# EEZ_DIB_MCU_r2B4.net
KiCad netlist of a schematic drawn in EAGLE
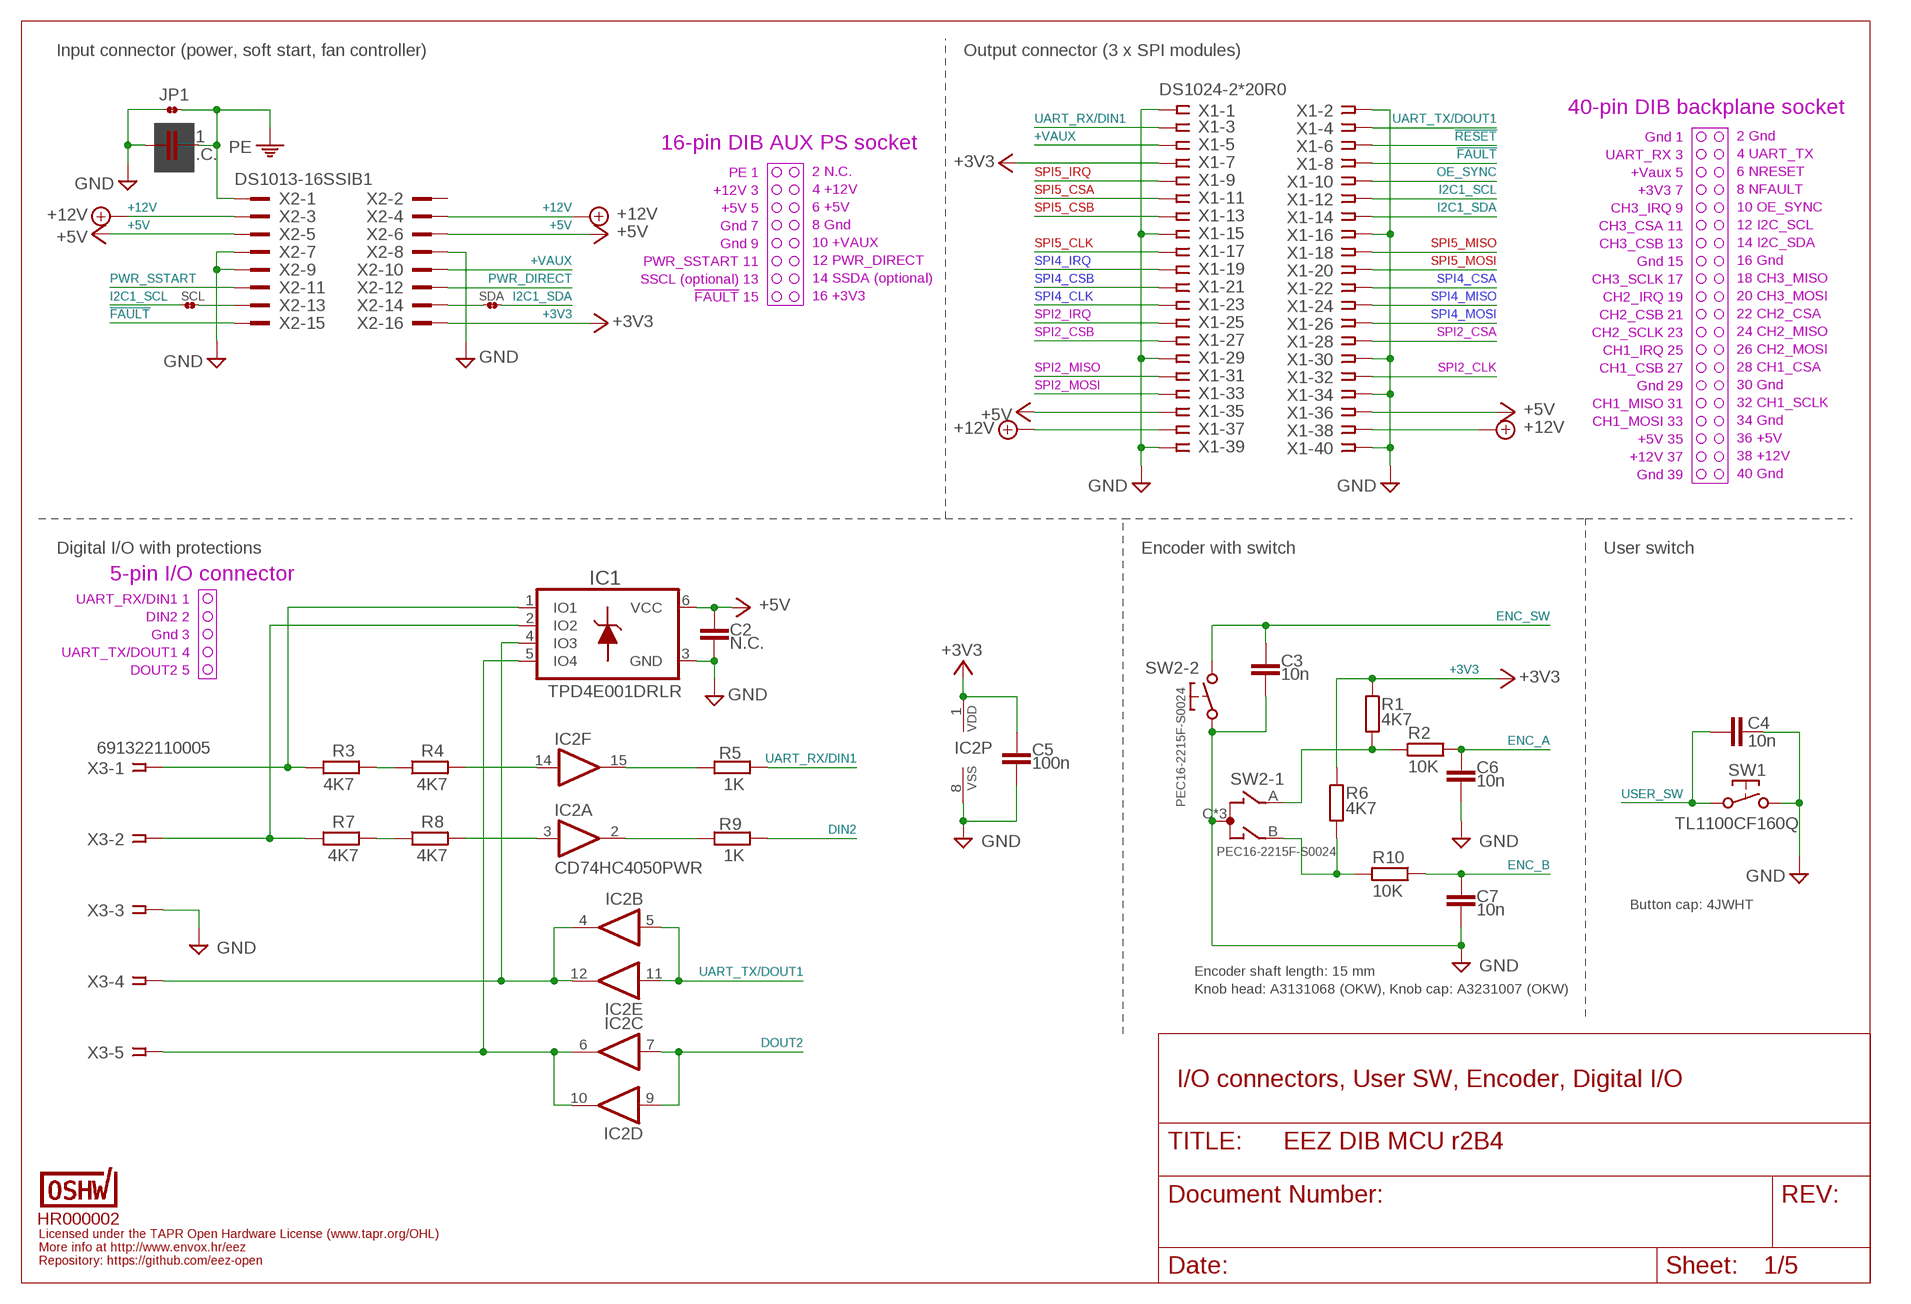
[diagram p0: schematic, sheet 1]
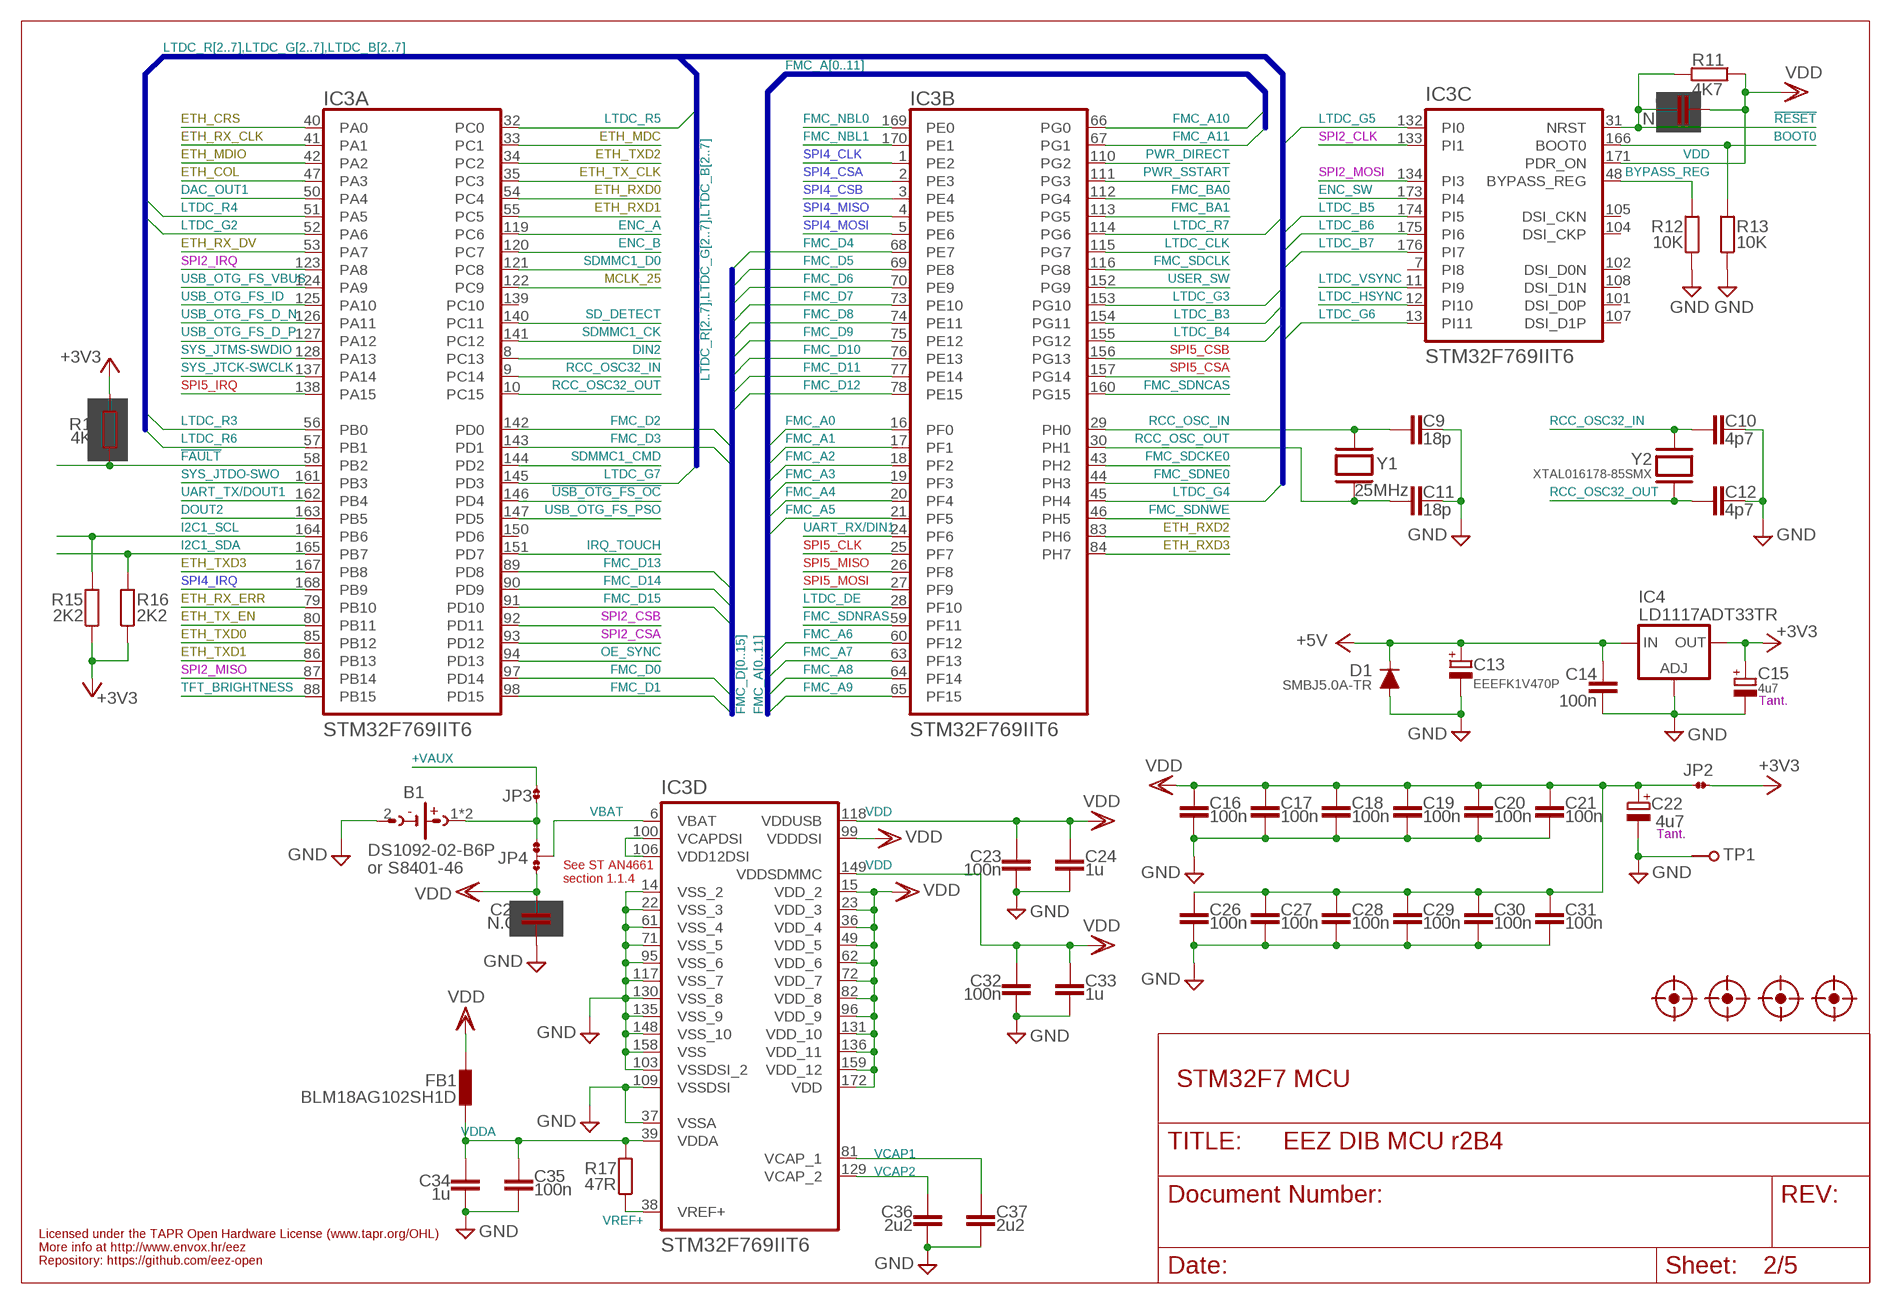
[diagram p1: schematic, sheet 2]
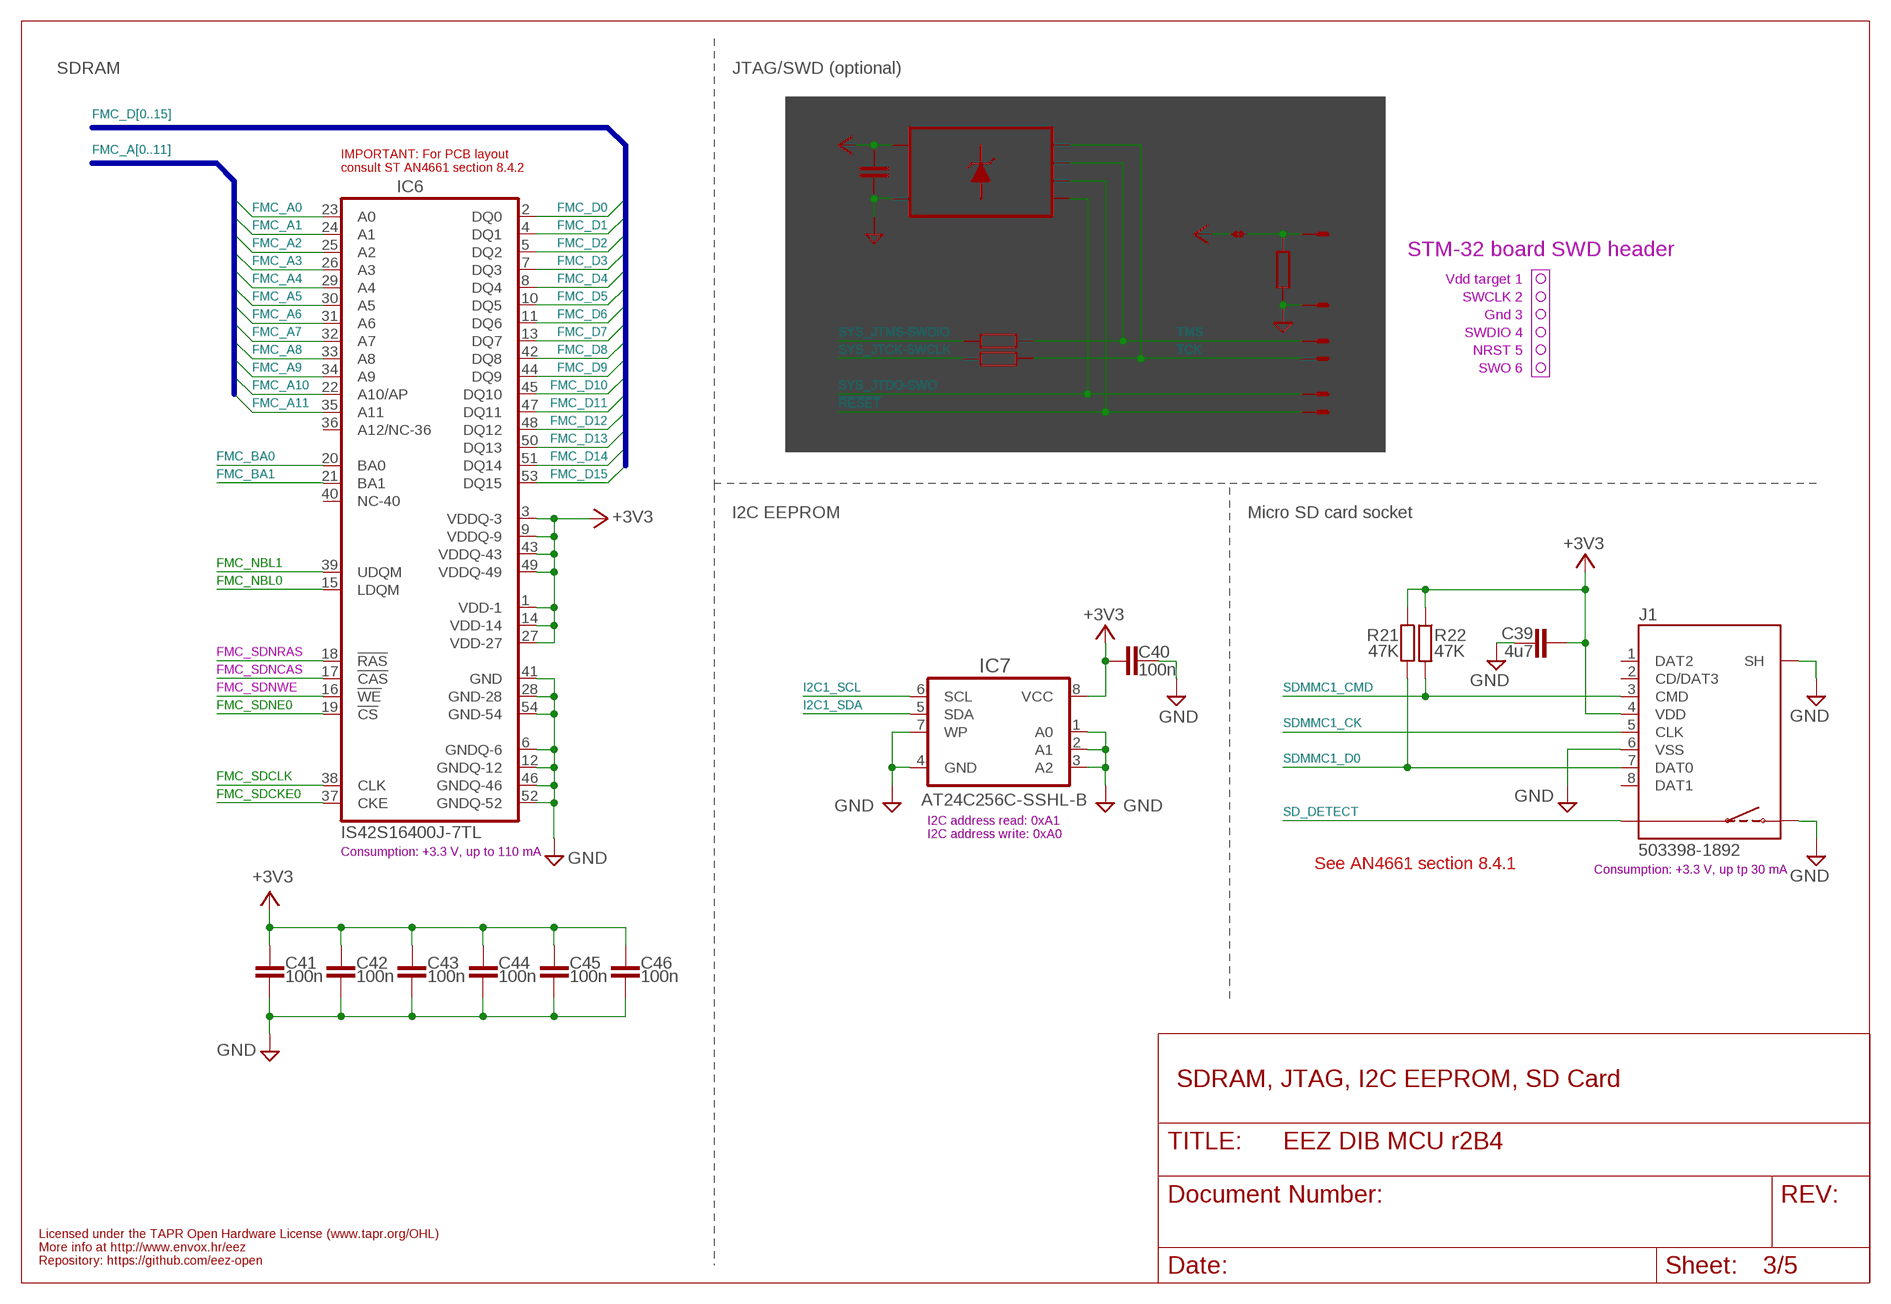
[diagram p2: schematic, sheet 3]
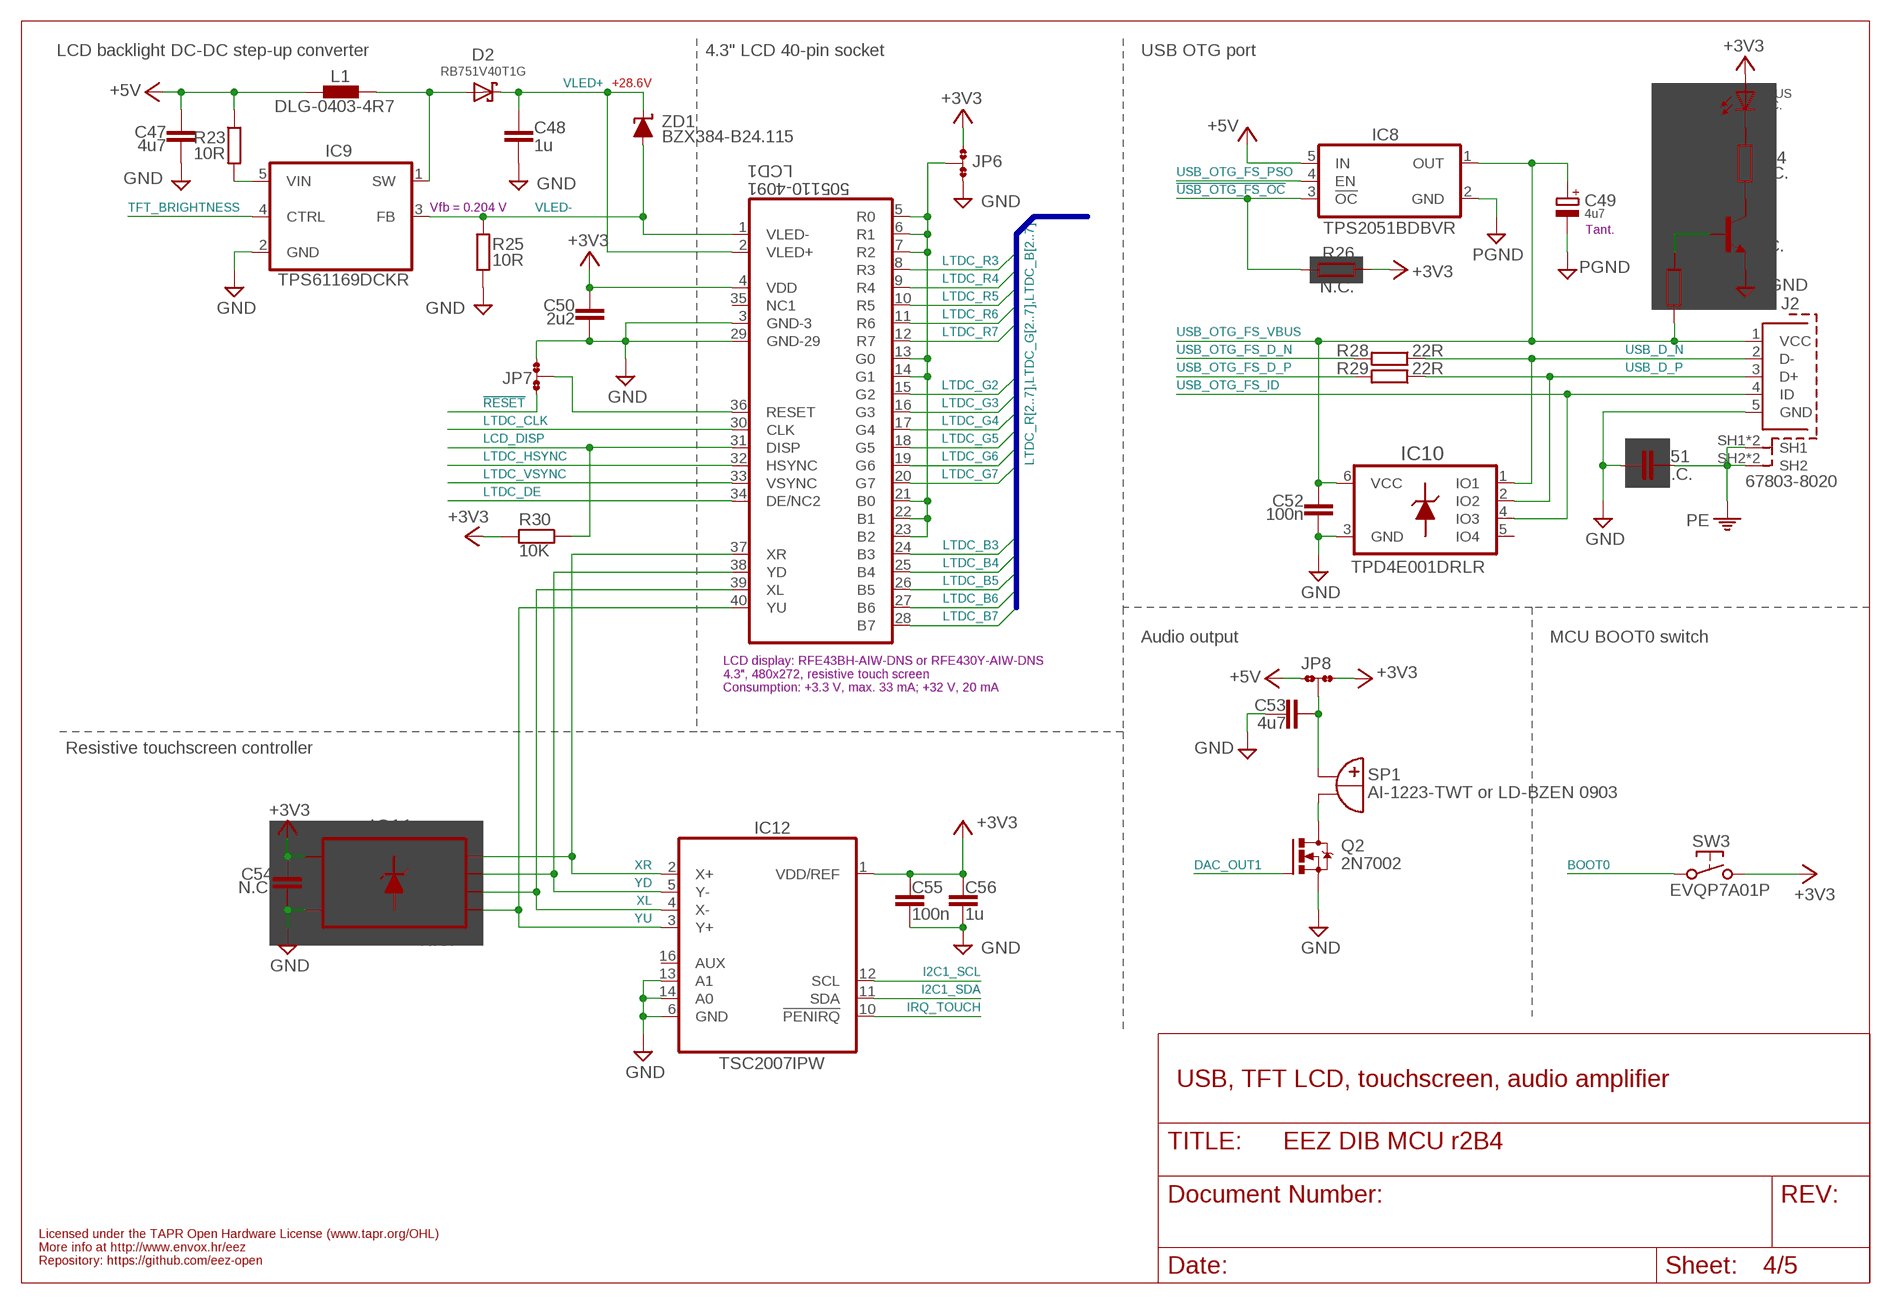
[diagram p3: schematic, sheet 4]
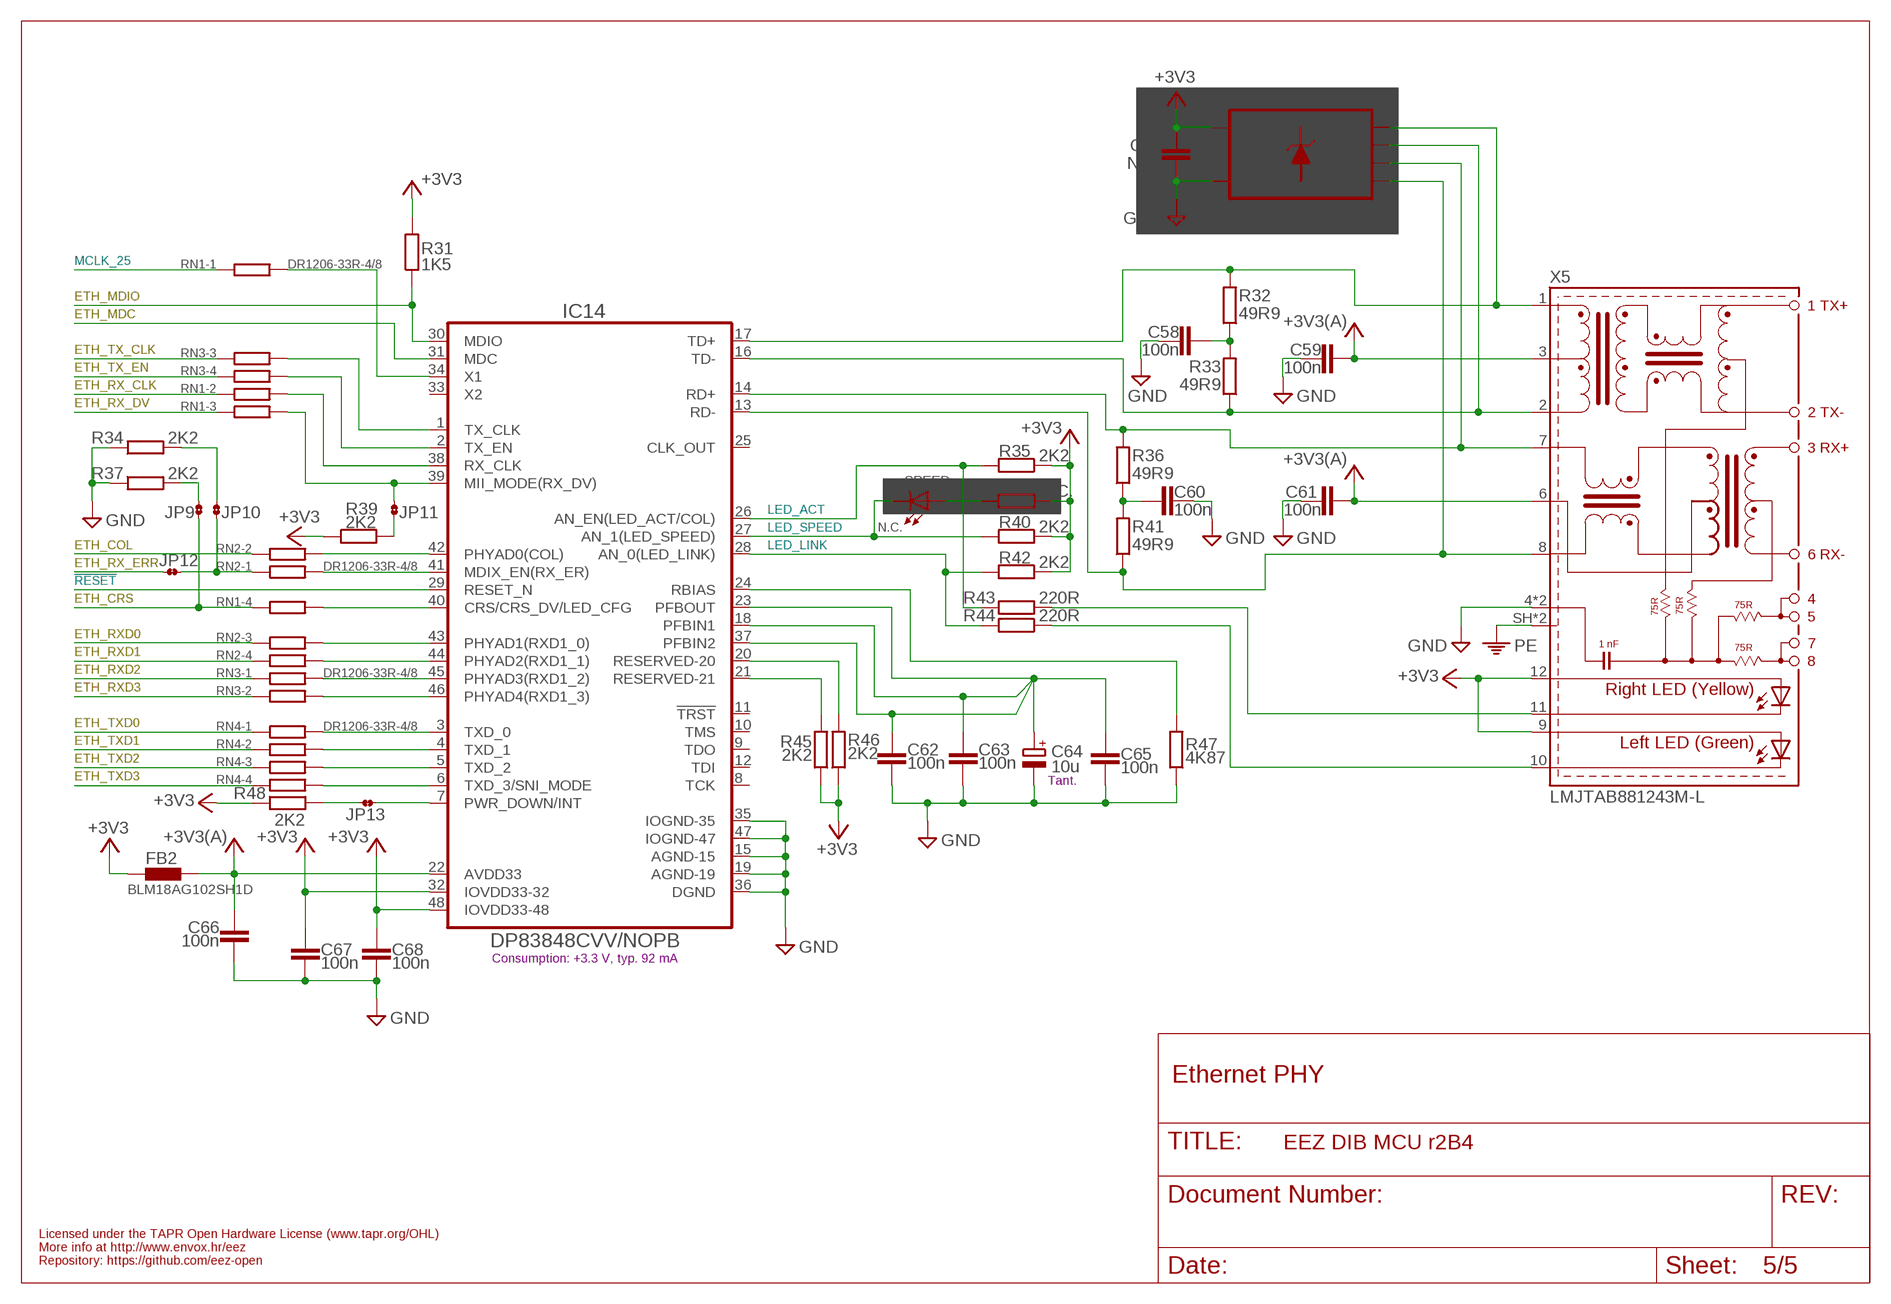
[diagram p4: schematic, sheet 5]

(export (version "E")
  (design (tool "Eeschema 10.0.6"))
  (components
    (comp (ref "B1")
      (value "DS1092-02-B6P")
      (footprint "eagle-import:S8401-46")
      (libsource (lib "eagle-import") (part "CELL_BATTERYVERT"))
    )
    (comp (ref "C8")
      (value "N.C.")
      (footprint "eagle-import:C0805")
      (libsource (lib "eagle-import") (part "C-EUC0805"))
    )
    (comp (ref "C9")
      (value "18p")
      (footprint "eagle-import:C0603")
      (libsource (lib "eagle-import") (part "C-EUC0603"))
    )
    (comp (ref "C10")
      (value "4p7")
      (footprint "eagle-import:C0603")
      (libsource (lib "eagle-import") (part "C-EUC0603"))
    )
    (comp (ref "C11")
      (value "18p")
      (footprint "eagle-import:C0603")
      (libsource (lib "eagle-import") (part "C-EUC0603"))
    )
    (comp (ref "C12")
      (value "4p7")
      (footprint "eagle-import:C0603")
      (libsource (lib "eagle-import") (part "C-EUC0603"))
    )
    (comp (ref "C13")
      (value "EEEFK1V470P")
      (footprint "eagle-import:CAPAE660X610N")
      (libsource (lib "eagle-import") (part "ECAPPANASONIC_H"))
    )
    (comp (ref "C14")
      (value "100n")
      (footprint "eagle-import:C0603")
      (libsource (lib "eagle-import") (part "C-EUC0603"))
    )
    (comp (ref "C15")
      (value "4u7")
      (footprint "eagle-import:EC1206")
      (libsource (lib "eagle-import") (part "ECAP1206"))
    )
    (comp (ref "C16")
      (value "100n")
      (footprint "eagle-import:C0603")
      (libsource (lib "eagle-import") (part "C-EUC0603"))
    )
    (comp (ref "C17")
      (value "100n")
      (footprint "eagle-import:C0603")
      (libsource (lib "eagle-import") (part "C-EUC0603"))
    )
    (comp (ref "C18")
      (value "100n")
      (footprint "eagle-import:C0603")
      (libsource (lib "eagle-import") (part "C-EUC0603"))
    )
    (comp (ref "C19")
      (value "100n")
      (footprint "eagle-import:C0603")
      (libsource (lib "eagle-import") (part "C-EUC0603"))
    )
    (comp (ref "C20")
      (value "100n")
      (footprint "eagle-import:C0603")
      (libsource (lib "eagle-import") (part "C-EUC0603"))
    )
    (comp (ref "C21")
      (value "100n")
      (footprint "eagle-import:C0603")
      (libsource (lib "eagle-import") (part "C-EUC0603"))
    )
    (comp (ref "C22")
      (value "4u7")
      (footprint "eagle-import:EC1206")
      (libsource (lib "eagle-import") (part "ECAP1206"))
    )
    (comp (ref "C23")
      (value "100n")
      (footprint "eagle-import:C0603")
      (libsource (lib "eagle-import") (part "C-EUC0603"))
    )
    (comp (ref "C24")
      (value "1u")
      (footprint "eagle-import:C0805")
      (libsource (lib "eagle-import") (part "C-EUC0805"))
    )
    (comp (ref "C25")
      (value "N.C.")
      (footprint "eagle-import:C0603")
      (libsource (lib "eagle-import") (part "C-EUC0603"))
    )
    (comp (ref "C26")
      (value "100n")
      (footprint "eagle-import:C0603")
      (libsource (lib "eagle-import") (part "C-EUC0603"))
    )
    (comp (ref "C27")
      (value "100n")
      (footprint "eagle-import:C0603")
      (libsource (lib "eagle-import") (part "C-EUC0603"))
    )
    (comp (ref "C28")
      (value "100n")
      (footprint "eagle-import:C0603")
      (libsource (lib "eagle-import") (part "C-EUC0603"))
    )
    (comp (ref "C29")
      (value "100n")
      (footprint "eagle-import:C0603")
      (libsource (lib "eagle-import") (part "C-EUC0603"))
    )
    (comp (ref "C30")
      (value "100n")
      (footprint "eagle-import:C0603")
      (libsource (lib "eagle-import") (part "C-EUC0603"))
    )
    (comp (ref "C31")
      (value "100n")
      (footprint "eagle-import:C0603")
      (libsource (lib "eagle-import") (part "C-EUC0603"))
    )
    (comp (ref "C32")
      (value "100n")
      (footprint "eagle-import:C0603")
      (libsource (lib "eagle-import") (part "C-EUC0603"))
    )
    (comp (ref "C33")
      (value "1u")
      (footprint "eagle-import:C0805")
      (libsource (lib "eagle-import") (part "C-EUC0805"))
    )
    (comp (ref "C34")
      (value "1u")
      (footprint "eagle-import:C0805")
      (libsource (lib "eagle-import") (part "C-EUC0805"))
    )
    (comp (ref "C35")
      (value "100n")
      (footprint "eagle-import:C0603")
      (libsource (lib "eagle-import") (part "C-EUC0603"))
    )
    (comp (ref "C36")
      (value "2u2")
      (footprint "eagle-import:C0805")
      (libsource (lib "eagle-import") (part "C-EUC0805"))
    )
    (comp (ref "C37")
      (value "2u2")
      (footprint "eagle-import:C0805")
      (libsource (lib "eagle-import") (part "C-EUC0805"))
    )
    (comp (ref "D1")
      (value "SMBJ5.0A-TR")
      (footprint "eagle-import:DO214AA")
      (libsource (lib "eagle-import") (part "DIODEDO214AA"))
    )
    (comp (ref "FB1")
      (value "BLM18AG102SH1D")
      (footprint "eagle-import:BEAD0603")
      (libsource (lib "eagle-import") (part "FERRITE_BEAD0603"))
    )
    (comp (ref "FM1")
      (value "FIDUCIAL")
      (footprint "eagle-import:FIDUCIAL")
      (libsource (lib "eagle-import") (part "FIDUCIAL"))
    )
    (comp (ref "FM2")
      (value "FIDUCIAL")
      (footprint "eagle-import:FIDUCIAL")
      (libsource (lib "eagle-import") (part "FIDUCIAL"))
    )
    (comp (ref "FM3")
      (value "FIDUCIAL")
      (footprint "eagle-import:FIDUCIAL")
      (libsource (lib "eagle-import") (part "FIDUCIAL"))
    )
    (comp (ref "FM4")
      (value "FIDUCIAL")
      (footprint "eagle-import:FIDUCIAL")
      (libsource (lib "eagle-import") (part "FIDUCIAL"))
    )
    (comp (ref "IC3")
      (value "STM32F769IIT6")
      (footprint "eagle-import:LQFP-176_24X24MM")
      (fields
        (field (name "MANUFACTURER_PART_NUMBER") "stm32f769ixt")
        (field (name "COPYRIGHT") "Copyright C 2016 Accelerated Designs. All rights reserved")
      )
      (libsource (lib "eagle-import") (part "STM32F769IXT"))
    )
    (comp (ref "IC4")
      (value "LD1117ADT33TR")
      (footprint "eagle-import:DPACK")
      (libsource (lib "eagle-import") (part "LD117A?DT33TR"))
    )
    (comp (ref "JP2")
      (value "JP2-NOCUT")
      (footprint "eagle-import:JP2-NOCUT")
      (libsource (lib "eagle-import") (part "JP2-NOCUT"))
    )
    (comp (ref "JP3")
      (value "JP2-CUT")
      (footprint "eagle-import:JP2-CUT")
      (libsource (lib "eagle-import") (part "JP2-CUT"))
    )
    (comp (ref "JP4")
      (value "JP3-CUT")
      (footprint "eagle-import:JP3-CUT")
      (libsource (lib "eagle-import") (part "JP3-CUT"))
    )
    (comp (ref "R11")
      (value "4K7")
      (footprint "eagle-import:R0805")
      (libsource (lib "eagle-import") (part "R-EU_R0805"))
    )
    (comp (ref "R12")
      (value "10K")
      (footprint "eagle-import:R0805")
      (libsource (lib "eagle-import") (part "R-EU_R0805"))
    )
    (comp (ref "R13")
      (value "10K")
      (footprint "eagle-import:R0805")
      (libsource (lib "eagle-import") (part "R-EU_R0805"))
    )
    (comp (ref "R14")
      (value "4K7")
      (footprint "eagle-import:R0805")
      (libsource (lib "eagle-import") (part "R-EU_R0805"))
    )
    (comp (ref "R15")
      (value "2K2")
      (footprint "eagle-import:R0805")
      (libsource (lib "eagle-import") (part "R-EU_R0805"))
    )
    (comp (ref "R16")
      (value "2K2")
      (footprint "eagle-import:R0805")
      (libsource (lib "eagle-import") (part "R-EU_R0805"))
    )
    (comp (ref "R17")
      (value "47R")
      (footprint "eagle-import:R0805")
      (libsource (lib "eagle-import") (part "R-EU_R0805"))
    )
    (comp (ref "TP1")
      (value "PCB_TEST_TABSHIELD")
      (footprint "eagle-import:PCB_SHIELD_TAB")
      (libsource (lib "eagle-import") (part "PCB_TEST_TABSHIELD"))
    )
    (comp (ref "Y1")
      (value "25MHz")
      (footprint "eagle-import:HC-49_4H")
      (libsource (lib "eagle-import") (part "XTALSMD"))
    )
    (comp (ref "Y2")
      (value "XTAL016178-85SMX")
      (footprint "eagle-import:85SMX")
      (libsource (lib "eagle-import") (part "XTAL85SMX"))
    )
    (comp (ref "C57")
      (value "N.C.")
      (footprint "eagle-import:C0603")
      (libsource (lib "eagle-import") (part "C-EUC0603"))
    )
    (comp (ref "C58")
      (value "100n")
      (footprint "eagle-import:C0603")
      (libsource (lib "eagle-import") (part "C-EUC0603"))
    )
    (comp (ref "C59")
      (value "100n")
      (footprint "eagle-import:C0603")
      (libsource (lib "eagle-import") (part "C-EUC0603"))
    )
    (comp (ref "C60")
      (value "100n")
      (footprint "eagle-import:C0603")
      (libsource (lib "eagle-import") (part "C-EUC0603"))
    )
    (comp (ref "C61")
      (value "100n")
      (footprint "eagle-import:C0603")
      (libsource (lib "eagle-import") (part "C-EUC0603"))
    )
    (comp (ref "C62")
      (value "100n")
      (footprint "eagle-import:C0603")
      (libsource (lib "eagle-import") (part "C-EUC0603"))
    )
    (comp (ref "C63")
      (value "100n")
      (footprint "eagle-import:C0603")
      (libsource (lib "eagle-import") (part "C-EUC0603"))
    )
    (comp (ref "C64")
      (value "10u")
      (footprint "eagle-import:EC1206")
      (libsource (lib "eagle-import") (part "ECAP1206"))
    )
    (comp (ref "C65")
      (value "100n")
      (footprint "eagle-import:C0603")
      (libsource (lib "eagle-import") (part "C-EUC0603"))
    )
    (comp (ref "C66")
      (value "100n")
      (footprint "eagle-import:C0603")
      (libsource (lib "eagle-import") (part "C-EUC0603"))
    )
    (comp (ref "C67")
      (value "100n")
      (footprint "eagle-import:C0603")
      (libsource (lib "eagle-import") (part "C-EUC0603"))
    )
    (comp (ref "C68")
      (value "100n")
      (footprint "eagle-import:C0603")
      (libsource (lib "eagle-import") (part "C-EUC0603"))
    )
    (comp (ref "FB2")
      (value "BLM18AG102SH1D")
      (footprint "eagle-import:BEAD0603")
      (libsource (lib "eagle-import") (part "FERRITE_BEAD0603"))
    )
    (comp (ref "IC13")
      (value "N.C.")
      (footprint "eagle-import:DRL6")
      (libsource (lib "eagle-import") (part "TPD4E001-DRL"))
    )
    (comp (ref "IC14")
      (value "DP83848CVV/NOPB")
      (footprint "eagle-import:PT48")
      (libsource (lib "eagle-import") (part "DP83848CVV/NOPB"))
    )
    (comp (ref "JP9")
      (value "JP2-CUT")
      (footprint "eagle-import:JP2-CUT")
      (libsource (lib "eagle-import") (part "JP2-CUT"))
    )
    (comp (ref "JP10")
      (value "JP2-CUT")
      (footprint "eagle-import:JP2-CUT")
      (libsource (lib "eagle-import") (part "JP2-CUT"))
    )
    (comp (ref "JP11")
      (value "JP2-CUT")
      (footprint "eagle-import:JP2-CUT")
      (libsource (lib "eagle-import") (part "JP2-CUT"))
    )
    (comp (ref "JP12")
      (value "JP2-NOCUT")
      (footprint "eagle-import:JP2-NOCUT")
      (libsource (lib "eagle-import") (part "JP2-NOCUT"))
    )
    (comp (ref "JP13")
      (value "JP2-NOCUT")
      (footprint "eagle-import:JP2-NOCUT")
      (libsource (lib "eagle-import") (part "JP2-NOCUT"))
    )
    (comp (ref "R31")
      (value "1K5")
      (footprint "eagle-import:R0805")
      (libsource (lib "eagle-import") (part "R-EU_R0805"))
    )
    (comp (ref "R32")
      (value "49R9")
      (footprint "eagle-import:R0805")
      (libsource (lib "eagle-import") (part "R-EU_R0805"))
    )
    (comp (ref "R33")
      (value "49R9")
      (footprint "eagle-import:R0805")
      (libsource (lib "eagle-import") (part "R-EU_R0805"))
    )
    (comp (ref "R34")
      (value "2K2")
      (footprint "eagle-import:R0805")
      (libsource (lib "eagle-import") (part "R-EU_R0805"))
    )
    (comp (ref "R35")
      (value "2K2")
      (footprint "eagle-import:R0805")
      (libsource (lib "eagle-import") (part "R-EU_R0805"))
    )
    (comp (ref "R36")
      (value "49R9")
      (footprint "eagle-import:R0805")
      (libsource (lib "eagle-import") (part "R-EU_R0805"))
    )
    (comp (ref "R37")
      (value "2K2")
      (footprint "eagle-import:R0805")
      (libsource (lib "eagle-import") (part "R-EU_R0805"))
    )
    (comp (ref "R38")
      (value "N.C.")
      (footprint "eagle-import:R0805")
      (libsource (lib "eagle-import") (part "R-EU_R0805"))
    )
    (comp (ref "R39")
      (value "2K2")
      (footprint "eagle-import:R0805")
      (libsource (lib "eagle-import") (part "R-EU_R0805"))
    )
    (comp (ref "R40")
      (value "2K2")
      (footprint "eagle-import:R0805")
      (libsource (lib "eagle-import") (part "R-EU_R0805"))
    )
    (comp (ref "R41")
      (value "49R9")
      (footprint "eagle-import:R0805")
      (libsource (lib "eagle-import") (part "R-EU_R0805"))
    )
    (comp (ref "R42")
      (value "2K2")
      (footprint "eagle-import:R0805")
      (libsource (lib "eagle-import") (part "R-EU_R0805"))
    )
    (comp (ref "R43")
      (value "220R")
      (footprint "eagle-import:R0805")
      (libsource (lib "eagle-import") (part "R-EU_R0805"))
    )
    (comp (ref "R44")
      (value "220R")
      (footprint "eagle-import:R0805")
      (libsource (lib "eagle-import") (part "R-EU_R0805"))
    )
    (comp (ref "R45")
      (value "2K2")
      (footprint "eagle-import:R0805")
      (libsource (lib "eagle-import") (part "R-EU_R0805"))
    )
    (comp (ref "R46")
      (value "2K2")
      (footprint "eagle-import:R0805")
      (libsource (lib "eagle-import") (part "R-EU_R0805"))
    )
    (comp (ref "R47")
      (value "4K87")
      (footprint "eagle-import:R0805")
      (libsource (lib "eagle-import") (part "R-EU_R0805"))
    )
    (comp (ref "R48")
      (value "2K2")
      (footprint "eagle-import:R0805")
      (libsource (lib "eagle-import") (part "R-EU_R0805"))
    )
    (comp (ref "RN1")
      (value "DR1206-33R-4/8")
      (footprint "eagle-import:CAY16")
      (libsource (lib "eagle-import") (part "R_ARRAY4"))
    )
    (comp (ref "RN2")
      (value "DR1206-33R-4/8")
      (footprint "eagle-import:CAY16")
      (libsource (lib "eagle-import") (part "R_ARRAY4"))
    )
    (comp (ref "RN3")
      (value "DR1206-33R-4/8")
      (footprint "eagle-import:CAY16")
      (libsource (lib "eagle-import") (part "R_ARRAY4"))
    )
    (comp (ref "RN4")
      (value "DR1206-33R-4/8")
      (footprint "eagle-import:CAY16")
      (libsource (lib "eagle-import") (part "R_ARRAY4"))
    )
    (comp (ref "SPEED")
      (value "N.C.")
      (footprint "eagle-import:LED_0805")
      (libsource (lib "eagle-import") (part "LED0805"))
    )
    (comp (ref "X5")
      (value "LMJTAB881243M-L")
      (footprint "eagle-import:RJ45-TRAFO-LED")
      (libsource (lib "eagle-import") (part "RJ45-TRAFO-LED"))
    )
    (comp (ref "C47")
      (value "4u7")
      (footprint "eagle-import:C1206")
      (libsource (lib "eagle-import") (part "C-EUC1206"))
    )
    (comp (ref "C48")
      (value "1u")
      (footprint "eagle-import:C0805")
      (libsource (lib "eagle-import") (part "C-EUC0805"))
    )
    (comp (ref "C49")
      (value "4u7")
      (footprint "eagle-import:EC1206")
      (libsource (lib "eagle-import") (part "ECAP1206"))
    )
    (comp (ref "C50")
      (value "2u2")
      (footprint "eagle-import:C0805")
      (libsource (lib "eagle-import") (part "C-EUC0805"))
    )
    (comp (ref "C51")
      (value "N.C.")
      (footprint "eagle-import:C0805")
      (libsource (lib "eagle-import") (part "C-EUC0805"))
    )
    (comp (ref "C52")
      (value "100n")
      (footprint "eagle-import:C0603")
      (libsource (lib "eagle-import") (part "C-EUC0603"))
    )
    (comp (ref "C53")
      (value "4u7")
      (footprint "eagle-import:C1206")
      (libsource (lib "eagle-import") (part "C-EUC1206"))
    )
    (comp (ref "C54")
      (value "N.C.")
      (footprint "eagle-import:C0603")
      (libsource (lib "eagle-import") (part "C-EUC0603"))
    )
    (comp (ref "C55")
      (value "100n")
      (footprint "eagle-import:C0603")
      (libsource (lib "eagle-import") (part "C-EUC0603"))
    )
    (comp (ref "C56")
      (value "1u")
      (footprint "eagle-import:C0805")
      (libsource (lib "eagle-import") (part "C-EUC0805"))
    )
    (comp (ref "D2")
      (value "RB751V40T1G")
      (footprint "eagle-import:SOD323-R")
      (libsource (lib "eagle-import") (part "SCHOTTKYSOD-323R"))
    )
    (comp (ref "IC8")
      (value "TPS2051BDBVR")
      (footprint "eagle-import:DBV5")
      (libsource (lib "eagle-import") (part "TPS2051B"))
    )
    (comp (ref "IC9")
      (value "TPS61169DCKR")
      (footprint "eagle-import:DCK5")
      (fields (field (name "MANUFACTURER") "Texas Instruments"))
      (libsource (lib "eagle-import") (part "TPS61169DCKR"))
    )
    (comp (ref "IC10")
      (value "TPD4E001DRLR")
      (footprint "eagle-import:DRL6")
      (libsource (lib "eagle-import") (part "TPD4E001-DRL"))
    )
    (comp (ref "IC11")
      (value "N.C.")
      (footprint "eagle-import:DRL6")
      (libsource (lib "eagle-import") (part "TPD4E001-DRL"))
    )
    (comp (ref "IC12")
      (value "TSC2007IPW")
      (footprint "eagle-import:PW(R-PDSO-G16)")
      (libsource (lib "eagle-import") (part "TSC2007IPW"))
    )
    (comp (ref "J2")
      (value "67803-8020")
      (footprint "eagle-import:678038020")
      (libsource (lib "eagle-import") (part "678038020"))
    )
    (comp (ref "JP6")
      (value "JP3-CUT")
      (footprint "eagle-import:JP3-CUT")
      (libsource (lib "eagle-import") (part "JP3-CUT"))
    )
    (comp (ref "JP7")
      (value "JP3-CUT")
      (footprint "eagle-import:JP3-CUT")
      (libsource (lib "eagle-import") (part "JP3-CUT"))
    )
    (comp (ref "JP8")
      (value "JP3-CUT")
      (footprint "eagle-import:JP3-CUT")
      (libsource (lib "eagle-import") (part "JP3-CUT"))
    )
    (comp (ref "L1")
      (value "DLG-0403-4R7")
      (footprint "eagle-import:DE0403")
      (libsource (lib "eagle-import") (part "DE0403"))
    )
    (comp (ref "LCD1")
      (value "505110-4091")
      (footprint "eagle-import:FPC_40")
      (libsource (lib "eagle-import") (part "RFE430Y-AIW-DNS"))
    )
    (comp (ref "Q1")
      (value "N.C.")
      (footprint "eagle-import:SOT23-BEC")
      (libsource (lib "eagle-import") (part "-NPN-SOT23-BECMMBT5551LT1"))
    )
    (comp (ref "Q2")
      (value "2N7002")
      (footprint "eagle-import:SOT103P240X110-3N")
      (fields (field (name "MPN") "2N7002-7-F"))
      (libsource (lib "eagle-import") (part "2N7002"))
    )
    (comp (ref "R23")
      (value "10R")
      (footprint "eagle-import:R0805")
      (libsource (lib "eagle-import") (part "R-EU_R0805"))
    )
    (comp (ref "R24")
      (value "N.C.")
      (footprint "eagle-import:R0805")
      (libsource (lib "eagle-import") (part "R-EU_R0805"))
    )
    (comp (ref "R25")
      (value "10R")
      (footprint "eagle-import:R0805")
      (libsource (lib "eagle-import") (part "R-EU_R0805"))
    )
    (comp (ref "R26")
      (value "N.C.")
      (footprint "eagle-import:R0805")
      (libsource (lib "eagle-import") (part "R-EU_R0805"))
    )
    (comp (ref "R27")
      (value "N.C.")
      (footprint "eagle-import:R0805")
      (libsource (lib "eagle-import") (part "R-EU_R0805"))
    )
    (comp (ref "R28")
      (value "22R")
      (footprint "eagle-import:R0805")
      (libsource (lib "eagle-import") (part "R-EU_R0805"))
    )
    (comp (ref "R29")
      (value "22R")
      (footprint "eagle-import:R0805")
      (libsource (lib "eagle-import") (part "R-EU_R0805"))
    )
    (comp (ref "R30")
      (value "10K")
      (footprint "eagle-import:R0805")
      (libsource (lib "eagle-import") (part "R-EU_R0805"))
    )
    (comp (ref "SP1")
      (value "AI-1223-TWT or LD-BZEN 0903")
      (footprint "eagle-import:AI-1223-TWT_COMBO")
      (libsource (lib "eagle-import") (part "AI-1223-TWT-LDB0903"))
    )
    (comp (ref "SW3")
      (value "EVQP7A01P")
      (footprint "eagle-import:PANASONIC_EVQP")
      (libsource (lib "eagle-import") (part "EVQP7A01P"))
    )
    (comp (ref "VBUS")
      (value "N.C.")
      (footprint "eagle-import:LED_0805")
      (libsource (lib "eagle-import") (part "LED0805"))
    )
    (comp (ref "ZD1")
      (value "BZX384-B24.115")
      (footprint "eagle-import:SOD323-W")
      (libsource (lib "eagle-import") (part "ZENER-DIODESOD323"))
    )
    (comp (ref "C38")
      (value "N.C.")
      (footprint "eagle-import:C0603")
      (libsource (lib "eagle-import") (part "C-EUC0603"))
    )
    (comp (ref "C39")
      (value "4u7")
      (footprint "eagle-import:C1206")
      (libsource (lib "eagle-import") (part "C-EUC1206"))
    )
    (comp (ref "C40")
      (value "100n")
      (footprint "eagle-import:C0603")
      (libsource (lib "eagle-import") (part "C-EUC0603"))
    )
    (comp (ref "C41")
      (value "100n")
      (footprint "eagle-import:C0603")
      (libsource (lib "eagle-import") (part "C-EUC0603"))
    )
    (comp (ref "C42")
      (value "100n")
      (footprint "eagle-import:C0603")
      (libsource (lib "eagle-import") (part "C-EUC0603"))
    )
    (comp (ref "C43")
      (value "100n")
      (footprint "eagle-import:C0603")
      (libsource (lib "eagle-import") (part "C-EUC0603"))
    )
    (comp (ref "C44")
      (value "100n")
      (footprint "eagle-import:C0603")
      (libsource (lib "eagle-import") (part "C-EUC0603"))
    )
    (comp (ref "C45")
      (value "100n")
      (footprint "eagle-import:C0603")
      (libsource (lib "eagle-import") (part "C-EUC0603"))
    )
    (comp (ref "C46")
      (value "100n")
      (footprint "eagle-import:C0603")
      (libsource (lib "eagle-import") (part "C-EUC0603"))
    )
    (comp (ref "IC5")
      (value "N.C.")
      (footprint "eagle-import:DRL6")
      (libsource (lib "eagle-import") (part "TPD4E001-DRL"))
    )
    (comp (ref "IC6")
      (value "IS42S16400J-7TL")
      (footprint "eagle-import:TSOPII-54")
      (libsource (lib "eagle-import") (part "IS42S16400"))
    )
    (comp (ref "IC7")
      (value "AT24C256C-SSHL-B")
      (footprint "eagle-import:SOIC127P600X173-8N")
      (libsource (lib "eagle-import") (part "AT24CXXSOIC8"))
    )
    (comp (ref "J1")
      (value "503398-1892")
      (footprint "eagle-import:5033981892")
      (libsource (lib "eagle-import") (part "5033981892"))
    )
    (comp (ref "JP5")
      (value "JP2-CUT")
      (footprint "eagle-import:JP2-CUT")
      (libsource (lib "eagle-import") (part "JP2-CUT"))
    )
    (comp (ref "R18")
      (value "N.C.")
      (footprint "eagle-import:R0805")
      (libsource (lib "eagle-import") (part "R-EU_R0805"))
    )
    (comp (ref "R19")
      (value "N.C.")
      (footprint "eagle-import:R0805")
      (libsource (lib "eagle-import") (part "R-EU_R0805"))
    )
    (comp (ref "R20")
      (value "N.C.")
      (footprint "eagle-import:R0805")
      (libsource (lib "eagle-import") (part "R-EU_R0805"))
    )
    (comp (ref "R21")
      (value "47K")
      (footprint "eagle-import:R0805")
      (libsource (lib "eagle-import") (part "R-EU_R0805"))
    )
    (comp (ref "R22")
      (value "47K")
      (footprint "eagle-import:R0805")
      (libsource (lib "eagle-import") (part "R-EU_R0805"))
    )
    (comp (ref "X4")
      (value "N.C.")
      (footprint "eagle-import:22-23-2061")
      (fields (field (name "MF") "MOLEX") (field (name "MPN") "22-23-2061"))
      (libsource (lib "eagle-import") (part "22-23-2061"))
    )
    (comp (ref "C1")
      (value "N.C.")
      (footprint "eagle-import:C0805")
      (libsource (lib "eagle-import") (part "C-EUC0805"))
    )
    (comp (ref "C2")
      (value "N.C.")
      (footprint "eagle-import:C0603")
      (libsource (lib "eagle-import") (part "C-EUC0603"))
    )
    (comp (ref "C3")
      (value "10n")
      (footprint "eagle-import:C0805")
      (libsource (lib "eagle-import") (part "C-EUC0805"))
    )
    (comp (ref "C4")
      (value "10n")
      (footprint "eagle-import:C0805")
      (libsource (lib "eagle-import") (part "C-EUC0805"))
    )
    (comp (ref "C5")
      (value "100n")
      (footprint "eagle-import:C0603")
      (libsource (lib "eagle-import") (part "C-EUC0603"))
    )
    (comp (ref "C6")
      (value "10n")
      (footprint "eagle-import:C0805")
      (libsource (lib "eagle-import") (part "C-EUC0805"))
    )
    (comp (ref "C7")
      (value "10n")
      (footprint "eagle-import:C0805")
      (libsource (lib "eagle-import") (part "C-EUC0805"))
    )
    (comp (ref "IC1")
      (value "TPD4E001DRLR")
      (footprint "eagle-import:DRL6")
      (libsource (lib "eagle-import") (part "TPD4E001-DRL"))
    )
    (comp (ref "IC2")
      (value "CD74HC4050PWR")
      (footprint "eagle-import:PW16")
      (libsource (lib "eagle-import") (part "CD74HC4050PWR"))
    )
    (comp (ref "JP1")
      (value "JP2-NOCUT")
      (footprint "eagle-import:JP2-NOCUT")
      (libsource (lib "eagle-import") (part "JP2-NOCUT"))
    )
    (comp (ref "R1")
      (value "4K7")
      (footprint "eagle-import:R0805")
      (libsource (lib "eagle-import") (part "R-EU_R0805"))
    )
    (comp (ref "R2")
      (value "10K")
      (footprint "eagle-import:R0805")
      (libsource (lib "eagle-import") (part "R-EU_R0805"))
    )
    (comp (ref "R3")
      (value "4K7")
      (footprint "eagle-import:R0805")
      (libsource (lib "eagle-import") (part "R-EU_R0805"))
    )
    (comp (ref "R4")
      (value "4K7")
      (footprint "eagle-import:R0805")
      (libsource (lib "eagle-import") (part "R-EU_R0805"))
    )
    (comp (ref "R5")
      (value "1K")
      (footprint "eagle-import:R0805")
      (libsource (lib "eagle-import") (part "R-EU_R0805"))
    )
    (comp (ref "R6")
      (value "4K7")
      (footprint "eagle-import:R0805")
      (libsource (lib "eagle-import") (part "R-EU_R0805"))
    )
    (comp (ref "R7")
      (value "4K7")
      (footprint "eagle-import:R0805")
      (libsource (lib "eagle-import") (part "R-EU_R0805"))
    )
    (comp (ref "R8")
      (value "4K7")
      (footprint "eagle-import:R0805")
      (libsource (lib "eagle-import") (part "R-EU_R0805"))
    )
    (comp (ref "R9")
      (value "1K")
      (footprint "eagle-import:R0805")
      (libsource (lib "eagle-import") (part "R-EU_R0805"))
    )
    (comp (ref "R10")
      (value "10K")
      (footprint "eagle-import:R0805")
      (libsource (lib "eagle-import") (part "R-EU_R0805"))
    )
    (comp (ref "SCL")
      (value "JP2-NOCUT")
      (footprint "eagle-import:JP2-NOCUT")
      (libsource (lib "eagle-import") (part "JP2-NOCUT"))
    )
    (comp (ref "SDA")
      (value "JP2-NOCUT")
      (footprint "eagle-import:JP2-NOCUT")
      (libsource (lib "eagle-import") (part "JP2-NOCUT"))
    )
    (comp (ref "SW1")
      (value "TL1100CF160Q")
      (footprint "eagle-import:TL1100C")
      (libsource (lib "eagle-import") (part "TL1100C"))
    )
    (comp (ref "SW2")
      (value "PEC16-2215F-S0024")
      (footprint "eagle-import:PEC16-2215F")
      (libsource (lib "eagle-import") (part "ENCODER_SW-PEC16"))
    )
    (comp (ref "U$3")
      (value "HR000002")
      (footprint "eagle-import:CERT-SMALL-SILK")
      (libsource (lib "eagle-import") (part "CERT-SMALL"))
    )
    (comp (ref "X1")
      (value "DS1024-2*20R0")
      (footprint "eagle-import:ZL263-40DG")
      (libsource (lib "eagle-import") (part "ZL263-40DG"))
    )
    (comp (ref "X2")
      (value "DS1013-16SSIB1")
      (footprint "eagle-import:IDC-16PIN")
      (libsource (lib "eagle-import") (part "IDC-16PIN"))
    )
    (comp (ref "X3")
      (value "691322110005")
      (footprint "eagle-import:MC1,5_5-G-3,5")
      (libsource (lib "eagle-import") (part "MC1,5/5-G-3,5"))
    )
  )
  (nets
    (net (code "1") (name "+3V3") (class "Default")
      (node (ref "C15") (pin "+") (pinfunction "+_+") (pintype "passive"))
      (node (ref "C38") (pin "1") (pinfunction "1_1") (pintype "passive"))
      (node (ref "C39") (pin "1") (pinfunction "1_1") (pintype "passive"))
      (node (ref "C40") (pin "2") (pinfunction "2_2") (pintype "passive"))
      (node (ref "C41") (pin "1") (pinfunction "1_1") (pintype "passive"))
      (node (ref "C42") (pin "1") (pinfunction "1_1") (pintype "passive"))
      (node (ref "C43") (pin "1") (pinfunction "1_1") (pintype "passive"))
      (node (ref "C44") (pin "1") (pinfunction "1_1") (pintype "passive"))
      (node (ref "C45") (pin "1") (pinfunction "1_1") (pintype "passive"))
      (node (ref "C46") (pin "1") (pinfunction "1_1") (pintype "passive"))
      (node (ref "C5") (pin "1") (pinfunction "1_1") (pintype "passive"))
      (node (ref "C50") (pin "1") (pinfunction "1_1") (pintype "passive"))
      (node (ref "C54") (pin "2") (pinfunction "2_2") (pintype "passive"))
      (node (ref "C55") (pin "2") (pinfunction "2_2") (pintype "passive"))
      (node (ref "C56") (pin "2") (pinfunction "2_2") (pintype "passive"))
      (node (ref "C57") (pin "1") (pinfunction "1_1") (pintype "passive"))
      (node (ref "C67") (pin "1") (pinfunction "1_1") (pintype "passive"))
      (node (ref "C68") (pin "1") (pinfunction "1_1") (pintype "passive"))
      (node (ref "FB2") (pin "P$1") (pinfunction "1_P$1") (pintype "passive"))
      (node (ref "IC11") (pin "6") (pinfunction "VCC_6") (pintype "passive"))
      (node (ref "IC12") (pin "1") (pinfunction "VDD/REF_1") (pintype "passive"))
      (node (ref "IC13") (pin "6") (pinfunction "VCC_6") (pintype "passive"))
      (node (ref "IC14") (pin "32") (pinfunction "IOVDD33-32_32") (pintype "power_in"))
      (node (ref "IC14") (pin "48") (pinfunction "IOVDD33-48_48") (pintype "power_in"))
      (node (ref "IC2") (pin "1") (pinfunction "VDD_1") (pintype "power_in"))
      (node (ref "IC4") (pin "4") (pinfunction "OUT_4") (pintype "passive"))
      (node (ref "IC5") (pin "6") (pinfunction "VCC_6") (pintype "passive"))
      (node (ref "IC6") (pin "1") (pinfunction "VDD-1_1") (pintype "power_in"))
      (node (ref "IC6") (pin "14") (pinfunction "VDD-14_14") (pintype "power_in"))
      (node (ref "IC6") (pin "27") (pinfunction "VDD-27_27") (pintype "power_in"))
      (node (ref "IC6") (pin "3") (pinfunction "VDDQ-3_3") (pintype "power_in"))
      (node (ref "IC6") (pin "43") (pinfunction "VDDQ-43_43") (pintype "power_in"))
      (node (ref "IC6") (pin "49") (pinfunction "VDDQ-49_49") (pintype "power_in"))
      (node (ref "IC6") (pin "9") (pinfunction "VDDQ-9_9") (pintype "power_in"))
      (node (ref "IC7") (pin "8") (pinfunction "VCC_8") (pintype "power_in"))
      (node (ref "J1") (pin "4") (pinfunction "VDD_4") (pintype "power_in"))
      (node (ref "JP2") (pin "2") (pinfunction "2_2") (pintype "passive"))
      (node (ref "JP5") (pin "1") (pinfunction "1_1") (pintype "passive"))
      (node (ref "JP6") (pin "NO") (pinfunction "NO_NO") (pintype "passive"))
      (node (ref "JP8") (pin "NC") (pinfunction "NC_NC") (pintype "passive"))
      (node (ref "LCD1") (pin "4") (pinfunction "VDD_4") (pintype "power_in"))
      (node (ref "R1") (pin "1") (pinfunction "1_1") (pintype "passive"))
      (node (ref "R14") (pin "1") (pinfunction "1_1") (pintype "passive"))
      (node (ref "R15") (pin "1") (pinfunction "1_1") (pintype "passive"))
      (node (ref "R16") (pin "1") (pinfunction "1_1") (pintype "passive"))
      (node (ref "R21") (pin "1") (pinfunction "1_1") (pintype "passive"))
      (node (ref "R22") (pin "1") (pinfunction "1_1") (pintype "passive"))
      (node (ref "R26") (pin "2") (pinfunction "2_2") (pintype "passive"))
      (node (ref "R30") (pin "2") (pinfunction "2_2") (pintype "passive"))
      (node (ref "R31") (pin "2") (pinfunction "2_2") (pintype "passive"))
      (node (ref "R35") (pin "1") (pinfunction "1_1") (pintype "passive"))
      (node (ref "R38") (pin "1") (pinfunction "1_1") (pintype "passive"))
      (node (ref "R39") (pin "1") (pinfunction "1_1") (pintype "passive"))
      (node (ref "R40") (pin "1") (pinfunction "1_1") (pintype "passive"))
      (node (ref "R42") (pin "1") (pinfunction "1_1") (pintype "passive"))
      (node (ref "R45") (pin "1") (pinfunction "1_1") (pintype "passive"))
      (node (ref "R46") (pin "1") (pinfunction "1_1") (pintype "passive"))
      (node (ref "R48") (pin "1") (pinfunction "1_1") (pintype "passive"))
      (node (ref "R6") (pin "1") (pinfunction "1_1") (pintype "passive"))
      (node (ref "SW3") (pin "2.1") (pinfunction "2_2.1") (pintype "passive"))
      (node (ref "SW3") (pin "2.2") (pinfunction "2_2.2") (pintype "passive"))
      (node (ref "VBUS") (pin "A") (pinfunction "A_A") (pintype "passive"))
      (node (ref "X1") (pin "7") (pinfunction "1_7") (pintype "passive"))
      (node (ref "X2") (pin "16") (pinfunction "1_16") (pintype "passive"))
      (node (ref "X5") (pin "12") (pinfunction "YELLOW_A_12") (pintype "passive"))
      (node (ref "X5") (pin "9") (pinfunction "GREEN-A_9") (pintype "passive"))
    )
    (net (code "2") (name "+3V3(A)") (class "Default")
      (node (ref "C59") (pin "2") (pinfunction "2_2") (pintype "passive"))
      (node (ref "C61") (pin "2") (pinfunction "2_2") (pintype "passive"))
      (node (ref "C66") (pin "1") (pinfunction "1_1") (pintype "passive"))
      (node (ref "FB2") (pin "P$2") (pinfunction "2_P$2") (pintype "passive"))
      (node (ref "IC14") (pin "22") (pinfunction "AVDD33_22") (pintype "power_in"))
      (node (ref "X5") (pin "3") (pinfunction "CT_3") (pintype "input"))
      (node (ref "X5") (pin "6") (pinfunction "CR_6") (pintype "input"))
    )
    (net (code "3") (name "+5V") (class "Default")
      (node (ref "C13") (pin "1") (pinfunction "+_1") (pintype "passive"))
      (node (ref "C14") (pin "1") (pinfunction "1_1") (pintype "passive"))
      (node (ref "C2") (pin "1") (pinfunction "1_1") (pintype "passive"))
      (node (ref "C47") (pin "1") (pinfunction "1_1") (pintype "passive"))
      (node (ref "D1") (pin "C") (pinfunction "C_C") (pintype "passive"))
      (node (ref "IC1") (pin "6") (pinfunction "VCC_6") (pintype "passive"))
      (node (ref "IC4") (pin "3") (pinfunction "IN_3") (pintype "input"))
      (node (ref "IC8") (pin "5") (pinfunction "IN_5") (pintype "input"))
      (node (ref "JP8") (pin "NO") (pinfunction "NO_NO") (pintype "passive"))
      (node (ref "L1") (pin "1") (pinfunction "1_1") (pintype "passive"))
      (node (ref "R23") (pin "1") (pinfunction "1_1") (pintype "passive"))
      (node (ref "X1") (pin "35") (pinfunction "1_35") (pintype "passive"))
      (node (ref "X1") (pin "36") (pinfunction "1_36") (pintype "passive"))
      (node (ref "X2") (pin "5") (pinfunction "1_5") (pintype "passive"))
      (node (ref "X2") (pin "6") (pinfunction "1_6") (pintype "passive"))
    )
    (net (code "4") (name "+12V") (class "Default")
      (node (ref "X1") (pin "37") (pinfunction "1_37") (pintype "passive"))
      (node (ref "X1") (pin "38") (pinfunction "1_38") (pintype "passive"))
      (node (ref "X2") (pin "3") (pinfunction "1_3") (pintype "passive"))
      (node (ref "X2") (pin "4") (pinfunction "1_4") (pintype "passive"))
    )
    (net (code "5") (name "+VAUX") (class "Default")
      (node (ref "JP3") (pin "2") (pinfunction "2_2") (pintype "passive"))
      (node (ref "X1") (pin "5") (pinfunction "1_5") (pintype "passive"))
      (node (ref "X2") (pin "10") (pinfunction "1_10") (pintype "passive"))
    )
    (net (code "12") (name "BOOT0") (class "Default")
      (node (ref "IC3") (pin "166") (pinfunction "BOOT0_166") (pintype "input"))
      (node (ref "R13") (pin "2") (pinfunction "2_2") (pintype "passive"))
      (node (ref "SW3") (pin "1.1") (pinfunction "1_1.1") (pintype "passive"))
      (node (ref "SW3") (pin "1.2") (pinfunction "1_1.2") (pintype "passive"))
    )
    (net (code "13") (name "BYPASS_REG") (class "Default")
      (node (ref "IC3") (pin "48") (pinfunction "BYPASS_REG_48") (pintype "input"))
      (node (ref "R12") (pin "2") (pinfunction "2_2") (pintype "passive"))
    )
    (net (code "14") (name "DAC_OUT1") (class "Default")
      (node (ref "IC3") (pin "50") (pinfunction "PA4_50") (pintype "bidirectional"))
      (node (ref "Q2") (pin "1") (pinfunction "G_1") (pintype "passive"))
    )
    (net (code "15") (name "DIN2") (class "Default")
      (node (ref "IC3") (pin "8") (pinfunction "PC13_8") (pintype "bidirectional"))
      (node (ref "R9") (pin "2") (pinfunction "2_2") (pintype "passive"))
    )
    (net (code "16") (name "DOUT2") (class "Default")
      (node (ref "IC2") (pin "7") (pinfunction "I_7") (pintype "input"))
      (node (ref "IC2") (pin "9") (pinfunction "I_9") (pintype "input"))
      (node (ref "IC3") (pin "163") (pinfunction "PB5_163") (pintype "bidirectional"))
    )
    (net (code "17") (name "ENC_A") (class "Default")
      (node (ref "C6") (pin "2") (pinfunction "2_2") (pintype "passive"))
      (node (ref "IC3") (pin "119") (pinfunction "PC6_119") (pintype "bidirectional"))
      (node (ref "R2") (pin "1") (pinfunction "1_1") (pintype "passive"))
    )
    (net (code "18") (name "ENC_B") (class "Default")
      (node (ref "C7") (pin "1") (pinfunction "1_1") (pintype "passive"))
      (node (ref "IC3") (pin "120") (pinfunction "PC7_120") (pintype "bidirectional"))
      (node (ref "R10") (pin "1") (pinfunction "1_1") (pintype "passive"))
    )
    (net (code "19") (name "ENC_SW") (class "Default")
      (node (ref "C3") (pin "2") (pinfunction "2_2") (pintype "passive"))
      (node (ref "IC3") (pin "173") (pinfunction "PI4_173") (pintype "bidirectional"))
      (node (ref "SW2") (pin "E") (pinfunction "2_E") (pintype "passive"))
    )
    (net (code "20") (name "ETH_COL") (class "Default")
      (node (ref "IC3") (pin "47") (pinfunction "PA3_47") (pintype "bidirectional"))
      (node (ref "RN2") (pin "2") (pinfunction "1_2") (pintype "passive"))
    )
    (net (code "21") (name "ETH_CRS") (class "Default")
      (node (ref "IC3") (pin "40") (pinfunction "PA0_40") (pintype "bidirectional"))
      (node (ref "JP9") (pin "1") (pinfunction "1_1") (pintype "passive"))
      (node (ref "RN1") (pin "4") (pinfunction "1_4") (pintype "passive"))
    )
    (net (code "22") (name "ETH_MDC") (class "Default")
      (node (ref "IC14") (pin "31") (pinfunction "MDC_31") (pintype "input"))
      (node (ref "IC3") (pin "33") (pinfunction "PC1_33") (pintype "bidirectional"))
    )
    (net (code "23") (name "ETH_MDIO") (class "Default")
      (node (ref "IC14") (pin "30") (pinfunction "MDIO_30") (pintype "bidirectional"))
      (node (ref "IC3") (pin "42") (pinfunction "PA2_42") (pintype "bidirectional"))
      (node (ref "R31") (pin "1") (pinfunction "1_1") (pintype "passive"))
    )
    (net (code "24") (name "ETH_RXD0") (class "Default")
      (node (ref "IC3") (pin "54") (pinfunction "PC4_54") (pintype "bidirectional"))
      (node (ref "RN2") (pin "3") (pinfunction "1_3") (pintype "passive"))
    )
    (net (code "25") (name "ETH_RXD1") (class "Default")
      (node (ref "IC3") (pin "55") (pinfunction "PC5_55") (pintype "bidirectional"))
      (node (ref "RN2") (pin "4") (pinfunction "1_4") (pintype "passive"))
    )
    (net (code "26") (name "ETH_RXD2") (class "Default")
      (node (ref "IC3") (pin "83") (pinfunction "PH6_83") (pintype "bidirectional"))
      (node (ref "RN3") (pin "1") (pinfunction "1_1") (pintype "passive"))
    )
    (net (code "27") (name "ETH_RXD3") (class "Default")
      (node (ref "IC3") (pin "84") (pinfunction "PH7_84") (pintype "bidirectional"))
      (node (ref "RN3") (pin "2") (pinfunction "1_2") (pintype "passive"))
    )
    (net (code "28") (name "ETH_RX_CLK") (class "Default")
      (node (ref "IC3") (pin "41") (pinfunction "PA1_41") (pintype "bidirectional"))
      (node (ref "RN1") (pin "2") (pinfunction "1_2") (pintype "passive"))
    )
    (net (code "29") (name "ETH_RX_DV") (class "Default")
      (node (ref "IC3") (pin "53") (pinfunction "PA7_53") (pintype "bidirectional"))
      (node (ref "RN1") (pin "3") (pinfunction "1_3") (pintype "passive"))
    )
    (net (code "30") (name "ETH_RX_ERR") (class "Default")
      (node (ref "IC3") (pin "79") (pinfunction "PB10_79") (pintype "bidirectional"))
      (node (ref "JP12") (pin "2") (pinfunction "2_2") (pintype "passive"))
    )
    (net (code "31") (name "ETH_TXD0") (class "Default")
      (node (ref "IC3") (pin "85") (pinfunction "PB12_85") (pintype "bidirectional"))
      (node (ref "RN4") (pin "1") (pinfunction "1_1") (pintype "passive"))
    )
    (net (code "32") (name "ETH_TXD1") (class "Default")
      (node (ref "IC3") (pin "86") (pinfunction "PB13_86") (pintype "bidirectional"))
      (node (ref "RN4") (pin "2") (pinfunction "1_2") (pintype "passive"))
    )
    (net (code "33") (name "ETH_TXD2") (class "Default")
      (node (ref "IC3") (pin "34") (pinfunction "PC2_34") (pintype "bidirectional"))
      (node (ref "RN4") (pin "3") (pinfunction "1_3") (pintype "passive"))
    )
    (net (code "34") (name "ETH_TXD3") (class "Default")
      (node (ref "IC3") (pin "167") (pinfunction "PB8_167") (pintype "bidirectional"))
      (node (ref "RN4") (pin "4") (pinfunction "1_4") (pintype "passive"))
    )
    (net (code "35") (name "ETH_TX_CLK") (class "Default")
      (node (ref "IC3") (pin "35") (pinfunction "PC3_35") (pintype "bidirectional"))
      (node (ref "RN3") (pin "3") (pinfunction "1_3") (pintype "passive"))
    )
    (net (code "36") (name "ETH_TX_EN") (class "Default")
      (node (ref "IC3") (pin "80") (pinfunction "PB11_80") (pintype "bidirectional"))
      (node (ref "RN3") (pin "4") (pinfunction "1_4") (pintype "passive"))
    )
    (net (code "37") (name "FMC_A0") (class "Default")
      (node (ref "IC3") (pin "16") (pinfunction "PF0_16") (pintype "bidirectional"))
      (node (ref "IC6") (pin "23") (pinfunction "A0_23") (pintype "input"))
    )
    (net (code "38") (name "FMC_A1") (class "Default")
      (node (ref "IC3") (pin "17") (pinfunction "PF1_17") (pintype "bidirectional"))
      (node (ref "IC6") (pin "24") (pinfunction "A1_24") (pintype "input"))
    )
    (net (code "39") (name "FMC_A2") (class "Default")
      (node (ref "IC3") (pin "18") (pinfunction "PF2_18") (pintype "bidirectional"))
      (node (ref "IC6") (pin "25") (pinfunction "A2_25") (pintype "input"))
    )
    (net (code "40") (name "FMC_A3") (class "Default")
      (node (ref "IC3") (pin "19") (pinfunction "PF3_19") (pintype "bidirectional"))
      (node (ref "IC6") (pin "26") (pinfunction "A3_26") (pintype "input"))
    )
    (net (code "41") (name "FMC_A4") (class "Default")
      (node (ref "IC3") (pin "20") (pinfunction "PF4_20") (pintype "bidirectional"))
      (node (ref "IC6") (pin "29") (pinfunction "A4_29") (pintype "input"))
    )
    (net (code "42") (name "FMC_A5") (class "Default")
      (node (ref "IC3") (pin "21") (pinfunction "PF5_21") (pintype "bidirectional"))
      (node (ref "IC6") (pin "30") (pinfunction "A5_30") (pintype "input"))
    )
    (net (code "43") (name "FMC_A6") (class "Default")
      (node (ref "IC3") (pin "60") (pinfunction "PF12_60") (pintype "bidirectional"))
      (node (ref "IC6") (pin "31") (pinfunction "A6_31") (pintype "input"))
    )
    (net (code "44") (name "FMC_A7") (class "Default")
      (node (ref "IC3") (pin "63") (pinfunction "PF13_63") (pintype "bidirectional"))
      (node (ref "IC6") (pin "32") (pinfunction "A7_32") (pintype "input"))
    )
    (net (code "45") (name "FMC_A8") (class "Default")
      (node (ref "IC3") (pin "64") (pinfunction "PF14_64") (pintype "bidirectional"))
      (node (ref "IC6") (pin "33") (pinfunction "A8_33") (pintype "input"))
    )
    (net (code "46") (name "FMC_A9") (class "Default")
      (node (ref "IC3") (pin "65") (pinfunction "PF15_65") (pintype "bidirectional"))
      (node (ref "IC6") (pin "34") (pinfunction "A9_34") (pintype "input"))
    )
    (net (code "47") (name "FMC_A10") (class "Default")
      (node (ref "IC3") (pin "66") (pinfunction "PG0_66") (pintype "bidirectional"))
      (node (ref "IC6") (pin "22") (pinfunction "A10/AP_22") (pintype "input"))
    )
    (net (code "48") (name "FMC_A11") (class "Default")
      (node (ref "IC3") (pin "67") (pinfunction "PG1_67") (pintype "bidirectional"))
      (node (ref "IC6") (pin "35") (pinfunction "A11_35") (pintype "input"))
    )
    (net (code "49") (name "FMC_BA0") (class "Default")
      (node (ref "IC3") (pin "112") (pinfunction "PG4_112") (pintype "bidirectional"))
      (node (ref "IC6") (pin "20") (pinfunction "BA0_20") (pintype "input"))
    )
    (net (code "50") (name "FMC_BA1") (class "Default")
      (node (ref "IC3") (pin "113") (pinfunction "PG5_113") (pintype "bidirectional"))
      (node (ref "IC6") (pin "21") (pinfunction "BA1_21") (pintype "input"))
    )
    (net (code "51") (name "FMC_D0") (class "Default")
      (node (ref "IC3") (pin "97") (pinfunction "PD14_97") (pintype "bidirectional"))
      (node (ref "IC6") (pin "2") (pinfunction "DQ0_2") (pintype "bidirectional"))
    )
    (net (code "52") (name "FMC_D1") (class "Default")
      (node (ref "IC3") (pin "98") (pinfunction "PD15_98") (pintype "bidirectional"))
      (node (ref "IC6") (pin "4") (pinfunction "DQ1_4") (pintype "bidirectional"))
    )
    (net (code "53") (name "FMC_D2") (class "Default")
      (node (ref "IC3") (pin "142") (pinfunction "PD0_142") (pintype "bidirectional"))
      (node (ref "IC6") (pin "5") (pinfunction "DQ2_5") (pintype "bidirectional"))
    )
    (net (code "54") (name "FMC_D3") (class "Default")
      (node (ref "IC3") (pin "143") (pinfunction "PD1_143") (pintype "bidirectional"))
      (node (ref "IC6") (pin "7") (pinfunction "DQ3_7") (pintype "bidirectional"))
    )
    (net (code "55") (name "FMC_D4") (class "Default")
      (node (ref "IC3") (pin "68") (pinfunction "PE7_68") (pintype "bidirectional"))
      (node (ref "IC6") (pin "8") (pinfunction "DQ4_8") (pintype "bidirectional"))
    )
    (net (code "56") (name "FMC_D5") (class "Default")
      (node (ref "IC3") (pin "69") (pinfunction "PE8_69") (pintype "bidirectional"))
      (node (ref "IC6") (pin "10") (pinfunction "DQ5_10") (pintype "bidirectional"))
    )
    (net (code "57") (name "FMC_D6") (class "Default")
      (node (ref "IC3") (pin "70") (pinfunction "PE9_70") (pintype "bidirectional"))
      (node (ref "IC6") (pin "11") (pinfunction "DQ6_11") (pintype "bidirectional"))
    )
    (net (code "58") (name "FMC_D7") (class "Default")
      (node (ref "IC3") (pin "73") (pinfunction "PE10_73") (pintype "bidirectional"))
      (node (ref "IC6") (pin "13") (pinfunction "DQ7_13") (pintype "bidirectional"))
    )
    (net (code "59") (name "FMC_D8") (class "Default")
      (node (ref "IC3") (pin "74") (pinfunction "PE11_74") (pintype "bidirectional"))
      (node (ref "IC6") (pin "42") (pinfunction "DQ8_42") (pintype "bidirectional"))
    )
    (net (code "60") (name "FMC_D9") (class "Default")
      (node (ref "IC3") (pin "75") (pinfunction "PE12_75") (pintype "bidirectional"))
      (node (ref "IC6") (pin "44") (pinfunction "DQ9_44") (pintype "bidirectional"))
    )
    (net (code "61") (name "FMC_D10") (class "Default")
      (node (ref "IC3") (pin "76") (pinfunction "PE13_76") (pintype "bidirectional"))
      (node (ref "IC6") (pin "45") (pinfunction "DQ10_45") (pintype "bidirectional"))
    )
    (net (code "62") (name "FMC_D11") (class "Default")
      (node (ref "IC3") (pin "77") (pinfunction "PE14_77") (pintype "bidirectional"))
      (node (ref "IC6") (pin "47") (pinfunction "DQ11_47") (pintype "bidirectional"))
    )
    (net (code "63") (name "FMC_D12") (class "Default")
      (node (ref "IC3") (pin "78") (pinfunction "PE15_78") (pintype "bidirectional"))
      (node (ref "IC6") (pin "48") (pinfunction "DQ12_48") (pintype "bidirectional"))
    )
    (net (code "64") (name "FMC_D13") (class "Default")
      (node (ref "IC3") (pin "89") (pinfunction "PD8_89") (pintype "bidirectional"))
      (node (ref "IC6") (pin "50") (pinfunction "DQ13_50") (pintype "bidirectional"))
    )
    (net (code "65") (name "FMC_D14") (class "Default")
      (node (ref "IC3") (pin "90") (pinfunction "PD9_90") (pintype "bidirectional"))
      (node (ref "IC6") (pin "51") (pinfunction "DQ14_51") (pintype "bidirectional"))
    )
    (net (code "66") (name "FMC_D15") (class "Default")
      (node (ref "IC3") (pin "91") (pinfunction "PD10_91") (pintype "bidirectional"))
      (node (ref "IC6") (pin "53") (pinfunction "DQ15_53") (pintype "bidirectional"))
    )
    (net (code "67") (name "FMC_NBL0") (class "Default")
      (node (ref "IC3") (pin "169") (pinfunction "PE0_169") (pintype "bidirectional"))
      (node (ref "IC6") (pin "15") (pinfunction "LDQM_15") (pintype "input"))
    )
    (net (code "68") (name "FMC_NBL1") (class "Default")
      (node (ref "IC3") (pin "170") (pinfunction "PE1_170") (pintype "bidirectional"))
      (node (ref "IC6") (pin "39") (pinfunction "UDQM_39") (pintype "input"))
    )
    (net (code "69") (name "FMC_SDCKE0") (class "Default")
      (node (ref "IC3") (pin "43") (pinfunction "PH2_43") (pintype "bidirectional"))
      (node (ref "IC6") (pin "37") (pinfunction "CKE_37") (pintype "input"))
    )
    (net (code "70") (name "FMC_SDCLK") (class "Default")
      (node (ref "IC3") (pin "116") (pinfunction "PG8_116") (pintype "bidirectional"))
      (node (ref "IC6") (pin "38") (pinfunction "CLK_38") (pintype "input"))
    )
    (net (code "71") (name "FMC_SDNCAS") (class "Default")
      (node (ref "IC3") (pin "160") (pinfunction "PG15_160") (pintype "bidirectional"))
      (node (ref "IC6") (pin "17") (pinfunction "~{CAS}_17") (pintype "input"))
    )
    (net (code "72") (name "FMC_SDNE0") (class "Default")
      (node (ref "IC3") (pin "44") (pinfunction "PH3_44") (pintype "bidirectional"))
      (node (ref "IC6") (pin "19") (pinfunction "~{CS}_19") (pintype "input"))
    )
    (net (code "73") (name "FMC_SDNRAS") (class "Default")
      (node (ref "IC3") (pin "59") (pinfunction "PF11_59") (pintype "bidirectional"))
      (node (ref "IC6") (pin "18") (pinfunction "~{RAS}_18") (pintype "input"))
    )
    (net (code "74") (name "FMC_SDNWE") (class "Default")
      (node (ref "IC3") (pin "46") (pinfunction "PH5_46") (pintype "bidirectional"))
      (node (ref "IC6") (pin "16") (pinfunction "~{WE}_16") (pintype "input"))
    )
    (net (code "75") (name "GND") (class "Default")
      (node (ref "B1") (pin "2") (pinfunction "-_2") (pintype "passive"))
      (node (ref "C1") (pin "2") (pinfunction "2_2") (pintype "passive"))
      (node (ref "C10") (pin "2") (pinfunction "2_2") (pintype "passive"))
      (node (ref "C11") (pin "1") (pinfunction "1_1") (pintype "passive"))
      (node (ref "C12") (pin "2") (pinfunction "2_2") (pintype "passive"))
      (node (ref "C13") (pin "2") (pinfunction "-_2") (pintype "passive"))
      (node (ref "C14") (pin "2") (pinfunction "2_2") (pintype "passive"))
      (node (ref "C15") (pin "-") (pinfunction "-_-") (pintype "passive"))
      (node (ref "C16") (pin "2") (pinfunction "2_2") (pintype "passive"))
      (node (ref "C17") (pin "2") (pinfunction "2_2") (pintype "passive"))
      (node (ref "C18") (pin "2") (pinfunction "2_2") (pintype "passive"))
      (node (ref "C19") (pin "2") (pinfunction "2_2") (pintype "passive"))
      (node (ref "C2") (pin "2") (pinfunction "2_2") (pintype "passive"))
      (node (ref "C20") (pin "2") (pinfunction "2_2") (pintype "passive"))
      (node (ref "C21") (pin "2") (pinfunction "2_2") (pintype "passive"))
      (node (ref "C22") (pin "-") (pinfunction "-_-") (pintype "passive"))
      (node (ref "C23") (pin "2") (pinfunction "2_2") (pintype "passive"))
      (node (ref "C24") (pin "2") (pinfunction "2_2") (pintype "passive"))
      (node (ref "C25") (pin "2") (pinfunction "2_2") (pintype "passive"))
      (node (ref "C26") (pin "2") (pinfunction "2_2") (pintype "passive"))
      (node (ref "C27") (pin "2") (pinfunction "2_2") (pintype "passive"))
      (node (ref "C28") (pin "2") (pinfunction "2_2") (pintype "passive"))
      (node (ref "C29") (pin "2") (pinfunction "2_2") (pintype "passive"))
      (node (ref "C3") (pin "1") (pinfunction "1_1") (pintype "passive"))
      (node (ref "C30") (pin "2") (pinfunction "2_2") (pintype "passive"))
      (node (ref "C31") (pin "2") (pinfunction "2_2") (pintype "passive"))
      (node (ref "C32") (pin "2") (pinfunction "2_2") (pintype "passive"))
      (node (ref "C33") (pin "2") (pinfunction "2_2") (pintype "passive"))
      (node (ref "C34") (pin "2") (pinfunction "2_2") (pintype "passive"))
      (node (ref "C35") (pin "2") (pinfunction "2_2") (pintype "passive"))
      (node (ref "C36") (pin "2") (pinfunction "2_2") (pintype "passive"))
      (node (ref "C37") (pin "2") (pinfunction "2_2") (pintype "passive"))
      (node (ref "C38") (pin "2") (pinfunction "2_2") (pintype "passive"))
      (node (ref "C39") (pin "2") (pinfunction "2_2") (pintype "passive"))
      (node (ref "C4") (pin "1") (pinfunction "1_1") (pintype "passive"))
      (node (ref "C40") (pin "1") (pinfunction "1_1") (pintype "passive"))
      (node (ref "C41") (pin "2") (pinfunction "2_2") (pintype "passive"))
      (node (ref "C42") (pin "2") (pinfunction "2_2") (pintype "passive"))
      (node (ref "C43") (pin "2") (pinfunction "2_2") (pintype "passive"))
      (node (ref "C44") (pin "2") (pinfunction "2_2") (pintype "passive"))
      (node (ref "C45") (pin "2") (pinfunction "2_2") (pintype "passive"))
      (node (ref "C46") (pin "2") (pinfunction "2_2") (pintype "passive"))
      (node (ref "C47") (pin "2") (pinfunction "2_2") (pintype "passive"))
      (node (ref "C48") (pin "2") (pinfunction "2_2") (pintype "passive"))
      (node (ref "C49") (pin "-") (pinfunction "-_-") (pintype "passive"))
      (node (ref "C5") (pin "2") (pinfunction "2_2") (pintype "passive"))
      (node (ref "C50") (pin "2") (pinfunction "2_2") (pintype "passive"))
      (node (ref "C51") (pin "2") (pinfunction "2_2") (pintype "passive"))
      (node (ref "C52") (pin "1") (pinfunction "1_1") (pintype "passive"))
      (node (ref "C53") (pin "1") (pinfunction "1_1") (pintype "passive"))
      (node (ref "C54") (pin "1") (pinfunction "1_1") (pintype "passive"))
      (node (ref "C55") (pin "1") (pinfunction "1_1") (pintype "passive"))
      (node (ref "C56") (pin "1") (pinfunction "1_1") (pintype "passive"))
      (node (ref "C57") (pin "2") (pinfunction "2_2") (pintype "passive"))
      (node (ref "C58") (pin "2") (pinfunction "2_2") (pintype "passive"))
      (node (ref "C59") (pin "1") (pinfunction "1_1") (pintype "passive"))
      (node (ref "C6") (pin "1") (pinfunction "1_1") (pintype "passive"))
      (node (ref "C60") (pin "2") (pinfunction "2_2") (pintype "passive"))
      (node (ref "C61") (pin "1") (pinfunction "1_1") (pintype "passive"))
      (node (ref "C62") (pin "2") (pinfunction "2_2") (pintype "passive"))
      (node (ref "C63") (pin "2") (pinfunction "2_2") (pintype "passive"))
      (node (ref "C64") (pin "-") (pinfunction "-_-") (pintype "passive"))
      (node (ref "C65") (pin "2") (pinfunction "2_2") (pintype "passive"))
      (node (ref "C66") (pin "2") (pinfunction "2_2") (pintype "passive"))
      (node (ref "C67") (pin "2") (pinfunction "2_2") (pintype "passive"))
      (node (ref "C68") (pin "2") (pinfunction "2_2") (pintype "passive"))
      (node (ref "C7") (pin "2") (pinfunction "2_2") (pintype "passive"))
      (node (ref "C9") (pin "1") (pinfunction "1_1") (pintype "passive"))
      (node (ref "D1") (pin "A") (pinfunction "A_A") (pintype "passive"))
      (node (ref "IC1") (pin "3") (pinfunction "GND_3") (pintype "power_in"))
      (node (ref "IC10") (pin "3") (pinfunction "GND_3") (pintype "power_in"))
      (node (ref "IC11") (pin "3") (pinfunction "GND_3") (pintype "power_in"))
      (node (ref "IC12") (pin "13") (pinfunction "A1_13") (pintype "input"))
      (node (ref "IC12") (pin "14") (pinfunction "A0_14") (pintype "input"))
      (node (ref "IC12") (pin "6") (pinfunction "GND_6") (pintype "passive"))
      (node (ref "IC13") (pin "3") (pinfunction "GND_3") (pintype "power_in"))
      (node (ref "IC14") (pin "15") (pinfunction "AGND-15_15") (pintype "power_in"))
      (node (ref "IC14") (pin "19") (pinfunction "AGND-19_19") (pintype "power_in"))
      (node (ref "IC14") (pin "35") (pinfunction "IOGND-35_35") (pintype "power_in"))
      (node (ref "IC14") (pin "36") (pinfunction "DGND_36") (pintype "power_in"))
      (node (ref "IC14") (pin "47") (pinfunction "IOGND-47_47") (pintype "power_in"))
      (node (ref "IC2") (pin "8") (pinfunction "VSS_8") (pintype "power_in"))
      (node (ref "IC3") (pin "103") (pinfunction "VSSDSI_2_103") (pintype "power_in"))
      (node (ref "IC3") (pin "109") (pinfunction "VSSDSI_109") (pintype "power_in"))
      (node (ref "IC3") (pin "117") (pinfunction "VSS_7_117") (pintype "power_in"))
      (node (ref "IC3") (pin "130") (pinfunction "VSS_8_130") (pintype "power_in"))
      (node (ref "IC3") (pin "135") (pinfunction "VSS_9_135") (pintype "power_in"))
      (node (ref "IC3") (pin "14") (pinfunction "VSS_2_14") (pintype "power_in"))
      (node (ref "IC3") (pin "148") (pinfunction "VSS_10_148") (pintype "power_in"))
      (node (ref "IC3") (pin "158") (pinfunction "VSS_158") (pintype "power_in"))
      (node (ref "IC3") (pin "22") (pinfunction "VSS_3_22") (pintype "power_in"))
      (node (ref "IC3") (pin "37") (pinfunction "VSSA_37") (pintype "power_in"))
      (node (ref "IC3") (pin "61") (pinfunction "VSS_4_61") (pintype "power_in"))
      (node (ref "IC3") (pin "71") (pinfunction "VSS_5_71") (pintype "power_in"))
      (node (ref "IC3") (pin "95") (pinfunction "VSS_6_95") (pintype "power_in"))
      (node (ref "IC4") (pin "1") (pinfunction "ADJ_1") (pintype "input"))
      (node (ref "IC5") (pin "3") (pinfunction "GND_3") (pintype "power_in"))
      (node (ref "IC6") (pin "12") (pinfunction "GNDQ-12_12") (pintype "power_in"))
      (node (ref "IC6") (pin "28") (pinfunction "GND-28_28") (pintype "power_in"))
      (node (ref "IC6") (pin "41") (pinfunction "GND_41") (pintype "power_in"))
      (node (ref "IC6") (pin "46") (pinfunction "GNDQ-46_46") (pintype "power_in"))
      (node (ref "IC6") (pin "52") (pinfunction "GNDQ-52_52") (pintype "power_in"))
      (node (ref "IC6") (pin "54") (pinfunction "GND-54_54") (pintype "power_in"))
      (node (ref "IC6") (pin "6") (pinfunction "GNDQ-6_6") (pintype "power_in"))
      (node (ref "IC7") (pin "1") (pinfunction "A0_1") (pintype "input"))
      (node (ref "IC7") (pin "2") (pinfunction "A1_2") (pintype "input"))
      (node (ref "IC7") (pin "3") (pinfunction "A2_3") (pintype "input"))
      (node (ref "IC7") (pin "4") (pinfunction "GND_4") (pintype "passive"))
      (node (ref "IC7") (pin "7") (pinfunction "WP_7") (pintype "input"))
      (node (ref "IC8") (pin "2") (pinfunction "GND_2") (pintype "power_in"))
      (node (ref "IC9") (pin "2") (pinfunction "GND_2") (pintype "power_in"))
      (node (ref "J1") (pin "6") (pinfunction "VSS_6") (pintype "power_in"))
      (node (ref "J1") (pin "S") (pinfunction "SH_S") (pintype "passive"))
      (node (ref "J1") (pin "S1") (pinfunction "SH_S1") (pintype "passive"))
      (node (ref "J1") (pin "S2") (pinfunction "SH_S2") (pintype "passive"))
      (node (ref "J1") (pin "SW2") (pinfunction "SW2_SW2") (pintype "passive"))
      (node (ref "J2") (pin "5") (pinfunction "GND_5") (pintype "passive"))
      (node (ref "JP1") (pin "1") (pinfunction "1_1") (pintype "passive"))
      (node (ref "JP6") (pin "NC") (pinfunction "NC_NC") (pintype "passive"))
      (node (ref "JP7") (pin "NC") (pinfunction "NC_NC") (pintype "passive"))
      (node (ref "LCD1") (pin "29") (pinfunction "GND-29_29") (pintype "power_in"))
      (node (ref "LCD1") (pin "3") (pinfunction "GND-3_3") (pintype "power_in"))
      (node (ref "Q1") (pin "E") (pinfunction "E_E") (pintype "passive"))
      (node (ref "Q2") (pin "2") (pinfunction "S_2") (pintype "passive"))
      (node (ref "R12") (pin "1") (pinfunction "1_1") (pintype "passive"))
      (node (ref "R13") (pin "1") (pinfunction "1_1") (pintype "passive"))
      (node (ref "R18") (pin "1") (pinfunction "1_1") (pintype "passive"))
      (node (ref "R25") (pin "2") (pinfunction "2_2") (pintype "passive"))
      (node (ref "R34") (pin "1") (pinfunction "1_1") (pintype "passive"))
      (node (ref "R37") (pin "1") (pinfunction "1_1") (pintype "passive"))
      (node (ref "R47") (pin "1") (pinfunction "1_1") (pintype "passive"))
      (node (ref "SW1") (pin "2") (pinfunction "2_2") (pintype "passive"))
      (node (ref "SW2") (pin "C") (pinfunction "C_C") (pintype "passive"))
      (node (ref "SW2") (pin "D") (pinfunction "1_D") (pintype "passive"))
      (node (ref "SW2") (pin "GND1") (pinfunction "C_GND1") (pintype "passive"))
      (node (ref "SW2") (pin "GND2") (pinfunction "C_GND2") (pintype "passive"))
      (node (ref "TP1") (pin "1") (pinfunction "P$1_1") (pintype "bidirectional"))
      (node (ref "X1") (pin "1") (pinfunction "1_1") (pintype "passive"))
      (node (ref "X1") (pin "15") (pinfunction "1_15") (pintype "passive"))
      (node (ref "X1") (pin "16") (pinfunction "1_16") (pintype "passive"))
      (node (ref "X1") (pin "2") (pinfunction "1_2") (pintype "passive"))
      (node (ref "X1") (pin "29") (pinfunction "1_29") (pintype "passive"))
      (node (ref "X1") (pin "30") (pinfunction "1_30") (pintype "passive"))
      (node (ref "X1") (pin "34") (pinfunction "1_34") (pintype "passive"))
      (node (ref "X1") (pin "39") (pinfunction "1_39") (pintype "passive"))
      (node (ref "X1") (pin "40") (pinfunction "1_40") (pintype "passive"))
      (node (ref "X2") (pin "7") (pinfunction "1_7") (pintype "passive"))
      (node (ref "X2") (pin "8") (pinfunction "1_8") (pintype "passive"))
      (node (ref "X2") (pin "9") (pinfunction "1_9") (pintype "passive"))
      (node (ref "X3") (pin "3") (pinfunction "1_3") (pintype "passive"))
      (node (ref "X4") (pin "3") (pinfunction "S_3") (pintype "passive"))
      (node (ref "X5") (pin "4") (pinfunction "GND_4") (pintype "passive"))
      (node (ref "X5") (pin "5") (pinfunction "GND_5") (pintype "passive"))
    )
    (net (code "76") (name "I2C1_SCL") (class "Default")
      (node (ref "IC12") (pin "12") (pinfunction "SCL_12") (pintype "bidirectional"))
      (node (ref "IC3") (pin "164") (pinfunction "PB6_164") (pintype "bidirectional"))
      (node (ref "IC7") (pin "6") (pinfunction "SCL_6") (pintype "bidirectional"))
      (node (ref "R15") (pin "2") (pinfunction "2_2") (pintype "passive"))
      (node (ref "SCL") (pin "1") (pinfunction "1_1") (pintype "passive"))
      (node (ref "X1") (pin "12") (pinfunction "1_12") (pintype "passive"))
    )
    (net (code "77") (name "I2C1_SDA") (class "Default")
      (node (ref "IC12") (pin "11") (pinfunction "SDA_11") (pintype "bidirectional"))
      (node (ref "IC3") (pin "165") (pinfunction "PB7_165") (pintype "bidirectional"))
      (node (ref "IC7") (pin "5") (pinfunction "SDA_5") (pintype "bidirectional"))
      (node (ref "R16") (pin "2") (pinfunction "2_2") (pintype "passive"))
      (node (ref "SDA") (pin "2") (pinfunction "2_2") (pintype "passive"))
      (node (ref "X1") (pin "14") (pinfunction "1_14") (pintype "passive"))
    )
    (net (code "78") (name "IRQ_TOUCH") (class "Default")
      (node (ref "IC12") (pin "10") (pinfunction "~{PENIRQ}_10") (pintype "output"))
      (node (ref "IC3") (pin "151") (pinfunction "PD7_151") (pintype "bidirectional"))
    )
    (net (code "79") (name "LCD_DISP") (class "Default")
      (node (ref "LCD1") (pin "31") (pinfunction "DISP_31") (pintype "input"))
      (node (ref "R30") (pin "1") (pinfunction "1_1") (pintype "passive"))
    )
    (net (code "80") (name "LED_ACT") (class "Default")
      (node (ref "IC14") (pin "26") (pinfunction "AN_EN(LED_ACT/COL)_26") (pintype "output"))
      (node (ref "R35") (pin "2") (pinfunction "2_2") (pintype "passive"))
      (node (ref "R43") (pin "2") (pinfunction "2_2") (pintype "passive"))
    )
    (net (code "81") (name "LED_LINK") (class "Default")
      (node (ref "IC14") (pin "28") (pinfunction "AN_0(LED_LINK)_28") (pintype "output"))
      (node (ref "R42") (pin "2") (pinfunction "2_2") (pintype "passive"))
      (node (ref "R44") (pin "2") (pinfunction "2_2") (pintype "passive"))
    )
    (net (code "82") (name "LED_SPEED") (class "Default")
      (node (ref "IC14") (pin "27") (pinfunction "AN_1(LED_SPEED)_27") (pintype "output"))
      (node (ref "R40") (pin "2") (pinfunction "2_2") (pintype "passive"))
      (node (ref "SPEED") (pin "C") (pinfunction "C_C") (pintype "passive"))
    )
    (net (code "83") (name "LTDC_B3") (class "Default")
      (node (ref "IC3") (pin "154") (pinfunction "PG11_154") (pintype "bidirectional"))
      (node (ref "LCD1") (pin "24") (pinfunction "B3_24") (pintype "input"))
    )
    (net (code "84") (name "LTDC_B4") (class "Default")
      (node (ref "IC3") (pin "155") (pinfunction "PG12_155") (pintype "bidirectional"))
      (node (ref "LCD1") (pin "25") (pinfunction "B4_25") (pintype "input"))
    )
    (net (code "85") (name "LTDC_B5") (class "Default")
      (node (ref "IC3") (pin "174") (pinfunction "PI5_174") (pintype "bidirectional"))
      (node (ref "LCD1") (pin "26") (pinfunction "B5_26") (pintype "input"))
    )
    (net (code "86") (name "LTDC_B6") (class "Default")
      (node (ref "IC3") (pin "175") (pinfunction "PI6_175") (pintype "bidirectional"))
      (node (ref "LCD1") (pin "27") (pinfunction "B6_27") (pintype "input"))
    )
    (net (code "87") (name "LTDC_B7") (class "Default")
      (node (ref "IC3") (pin "176") (pinfunction "PI7_176") (pintype "bidirectional"))
      (node (ref "LCD1") (pin "28") (pinfunction "B7_28") (pintype "input"))
    )
    (net (code "88") (name "LTDC_CLK") (class "Default")
      (node (ref "IC3") (pin "115") (pinfunction "PG7_115") (pintype "bidirectional"))
      (node (ref "LCD1") (pin "30") (pinfunction "CLK_30") (pintype "input"))
    )
    (net (code "89") (name "LTDC_DE") (class "Default")
      (node (ref "IC3") (pin "28") (pinfunction "PF10_28") (pintype "bidirectional"))
      (node (ref "LCD1") (pin "34") (pinfunction "DE/NC2_34") (pintype "passive"))
    )
    (net (code "90") (name "LTDC_G2") (class "Default")
      (node (ref "IC3") (pin "52") (pinfunction "PA6_52") (pintype "bidirectional"))
      (node (ref "LCD1") (pin "15") (pinfunction "G2_15") (pintype "input"))
    )
    (net (code "91") (name "LTDC_G3") (class "Default")
      (node (ref "IC3") (pin "153") (pinfunction "PG10_153") (pintype "bidirectional"))
      (node (ref "LCD1") (pin "16") (pinfunction "G3_16") (pintype "input"))
    )
    (net (code "92") (name "LTDC_G4") (class "Default")
      (node (ref "IC3") (pin "45") (pinfunction "PH4_45") (pintype "bidirectional"))
      (node (ref "LCD1") (pin "17") (pinfunction "G4_17") (pintype "input"))
    )
    (net (code "93") (name "LTDC_G5") (class "Default")
      (node (ref "IC3") (pin "132") (pinfunction "PI0_132") (pintype "bidirectional"))
      (node (ref "LCD1") (pin "18") (pinfunction "G5_18") (pintype "input"))
    )
    (net (code "94") (name "LTDC_G6") (class "Default")
      (node (ref "IC3") (pin "13") (pinfunction "PI11_13") (pintype "bidirectional"))
      (node (ref "LCD1") (pin "19") (pinfunction "G6_19") (pintype "input"))
    )
    (net (code "95") (name "LTDC_G7") (class "Default")
      (node (ref "IC3") (pin "145") (pinfunction "PD3_145") (pintype "bidirectional"))
      (node (ref "LCD1") (pin "20") (pinfunction "G7_20") (pintype "input"))
    )
    (net (code "96") (name "LTDC_HSYNC") (class "Default")
      (node (ref "IC3") (pin "12") (pinfunction "PI10_12") (pintype "bidirectional"))
      (node (ref "LCD1") (pin "32") (pinfunction "HSYNC_32") (pintype "input"))
    )
    (net (code "97") (name "LTDC_R3") (class "Default")
      (node (ref "IC3") (pin "56") (pinfunction "PB0_56") (pintype "bidirectional"))
      (node (ref "LCD1") (pin "8") (pinfunction "R3_8") (pintype "input"))
    )
    (net (code "98") (name "LTDC_R4") (class "Default")
      (node (ref "IC3") (pin "51") (pinfunction "PA5_51") (pintype "bidirectional"))
      (node (ref "LCD1") (pin "9") (pinfunction "R4_9") (pintype "input"))
    )
    (net (code "99") (name "LTDC_R5") (class "Default")
      (node (ref "IC3") (pin "32") (pinfunction "PC0_32") (pintype "bidirectional"))
      (node (ref "LCD1") (pin "10") (pinfunction "R5_10") (pintype "input"))
    )
    (net (code "100") (name "LTDC_R6") (class "Default")
      (node (ref "IC3") (pin "57") (pinfunction "PB1_57") (pintype "bidirectional"))
      (node (ref "LCD1") (pin "11") (pinfunction "R6_11") (pintype "input"))
    )
    (net (code "101") (name "LTDC_R7") (class "Default")
      (node (ref "IC3") (pin "114") (pinfunction "PG6_114") (pintype "bidirectional"))
      (node (ref "LCD1") (pin "12") (pinfunction "R7_12") (pintype "input"))
    )
    (net (code "102") (name "LTDC_VSYNC") (class "Default")
      (node (ref "IC3") (pin "11") (pinfunction "PI9_11") (pintype "bidirectional"))
      (node (ref "LCD1") (pin "33") (pinfunction "VSYNC_33") (pintype "input"))
    )
    (net (code "103") (name "MCLK_25") (class "Default")
      (node (ref "IC3") (pin "122") (pinfunction "PC9_122") (pintype "bidirectional"))
      (node (ref "RN1") (pin "1") (pinfunction "1_1") (pintype "passive"))
    )
    (net (code "104") (name "Net-(B1-+-Pad1)") (class "Default")
      (node (ref "B1") (pin "1") (pinfunction "+_1") (pintype "passive"))
      (node (ref "B1") (pin "3") (pinfunction "+_3") (pintype "passive"))
      (node (ref "JP3") (pin "1") (pinfunction "1_1") (pintype "passive"))
      (node (ref "JP4") (pin "NC") (pinfunction "NC_NC") (pintype "passive"))
    )
    (net (code "105") (name "Net-(C53-Pad2)") (class "Default")
      (node (ref "C53") (pin "2") (pinfunction "2_2") (pintype "passive"))
      (node (ref "JP8") (pin "COM") (pinfunction "COM_COM") (pintype "passive"))
      (node (ref "SP1") (pin "+B") (pinfunction "+_+B") (pintype "passive"))
      (node (ref "SP1") (pin "+B.1") (pinfunction "+_+B.1") (pintype "passive"))
    )
    (net (code "106") (name "Net-(C58-Pad1)") (class "Default")
      (node (ref "C58") (pin "1") (pinfunction "1_1") (pintype "passive"))
      (node (ref "R32") (pin "1") (pinfunction "1_1") (pintype "passive"))
      (node (ref "R33") (pin "2") (pinfunction "2_2") (pintype "passive"))
    )
    (net (code "107") (name "Net-(C60-Pad1)") (class "Default")
      (node (ref "C60") (pin "1") (pinfunction "1_1") (pintype "passive"))
      (node (ref "R36") (pin "1") (pinfunction "1_1") (pintype "passive"))
      (node (ref "R41") (pin "2") (pinfunction "2_2") (pintype "passive"))
    )
    (net (code "108") (name "Net-(IC1-IO1)") (class "Default")
      (node (ref "IC1") (pin "1") (pinfunction "IO1_1") (pintype "bidirectional"))
      (node (ref "R3") (pin "1") (pinfunction "1_1") (pintype "passive"))
      (node (ref "X3") (pin "1") (pinfunction "1_1") (pintype "passive"))
    )
    (net (code "109") (name "Net-(IC1-IO2)") (class "Default")
      (node (ref "IC1") (pin "2") (pinfunction "IO2_2") (pintype "bidirectional"))
      (node (ref "R7") (pin "1") (pinfunction "1_1") (pintype "passive"))
      (node (ref "X3") (pin "2") (pinfunction "1_2") (pintype "passive"))
    )
    (net (code "110") (name "Net-(IC1-IO3)") (class "Default")
      (node (ref "IC1") (pin "4") (pinfunction "IO3_4") (pintype "bidirectional"))
      (node (ref "IC2") (pin "12") (pinfunction "O_12") (pintype "output"))
      (node (ref "IC2") (pin "4") (pinfunction "O_4") (pintype "output"))
      (node (ref "X3") (pin "4") (pinfunction "1_4") (pintype "passive"))
    )
    (net (code "111") (name "Net-(IC1-IO4)") (class "Default")
      (node (ref "IC1") (pin "5") (pinfunction "IO4_5") (pintype "bidirectional"))
      (node (ref "IC2") (pin "10") (pinfunction "O_10") (pintype "output"))
      (node (ref "IC2") (pin "6") (pinfunction "O_6") (pintype "output"))
      (node (ref "X3") (pin "5") (pinfunction "1_5") (pintype "passive"))
    )
    (net (code "112") (name "Net-(IC2A-I)") (class "Default")
      (node (ref "IC2") (pin "3") (pinfunction "I_3") (pintype "input"))
      (node (ref "R8") (pin "2") (pinfunction "2_2") (pintype "passive"))
    )
    (net (code "113") (name "Net-(IC2A-O)") (class "Default")
      (node (ref "IC2") (pin "2") (pinfunction "O_2") (pintype "output"))
      (node (ref "R9") (pin "1") (pinfunction "1_1") (pintype "passive"))
    )
    (net (code "114") (name "Net-(IC2F-I)") (class "Default")
      (node (ref "IC2") (pin "14") (pinfunction "I_14") (pintype "input"))
      (node (ref "R4") (pin "2") (pinfunction "2_2") (pintype "passive"))
    )
    (net (code "115") (name "Net-(IC2F-O)") (class "Default")
      (node (ref "IC2") (pin "15") (pinfunction "O_15") (pintype "output"))
      (node (ref "R5") (pin "1") (pinfunction "1_1") (pintype "passive"))
    )
    (net (code "116") (name "Net-(IC3D-VCAPDSI)") (class "Default")
      (node (ref "IC3") (pin "100") (pinfunction "VCAPDSI_100") (pintype "power_in"))
      (node (ref "IC3") (pin "106") (pinfunction "VDD12DSI_106") (pintype "power_in"))
    )
    (net (code "117") (name "Net-(IC9-SW)") (class "Default")
      (node (ref "D2") (pin "A") (pinfunction "A_A") (pintype "passive"))
      (node (ref "IC9") (pin "1") (pinfunction "SW_1") (pintype "output"))
      (node (ref "L1") (pin "2") (pinfunction "2_2") (pintype "passive"))
    )
    (net (code "118") (name "Net-(IC9-VIN)") (class "Default")
      (node (ref "IC9") (pin "5") (pinfunction "VIN_5") (pintype "input"))
      (node (ref "R23") (pin "2") (pinfunction "2_2") (pintype "passive"))
    )
    (net (code "119") (name "Net-(IC13-IO1)") (class "Default")
      (node (ref "IC13") (pin "1") (pinfunction "IO1_1") (pintype "bidirectional"))
      (node (ref "IC14") (pin "17") (pinfunction "TD+_17") (pintype "bidirectional"))
      (node (ref "R32") (pin "2") (pinfunction "2_2") (pintype "passive"))
      (node (ref "X5") (pin "1") (pinfunction "TD+_1") (pintype "input"))
    )
    (net (code "120") (name "Net-(IC13-IO2)") (class "Default")
      (node (ref "IC13") (pin "2") (pinfunction "IO2_2") (pintype "bidirectional"))
      (node (ref "IC14") (pin "16") (pinfunction "TD-_16") (pintype "bidirectional"))
      (node (ref "R33") (pin "1") (pinfunction "1_1") (pintype "passive"))
      (node (ref "X5") (pin "2") (pinfunction "TD-_2") (pintype "input"))
    )
    (net (code "121") (name "Net-(IC13-IO3)") (class "Default")
      (node (ref "IC13") (pin "4") (pinfunction "IO3_4") (pintype "bidirectional"))
      (node (ref "IC14") (pin "14") (pinfunction "RD+_14") (pintype "bidirectional"))
      (node (ref "R36") (pin "2") (pinfunction "2_2") (pintype "passive"))
      (node (ref "X5") (pin "7") (pinfunction "RD+_7") (pintype "input"))
    )
    (net (code "122") (name "Net-(IC13-IO4)") (class "Default")
      (node (ref "IC13") (pin "5") (pinfunction "IO4_5") (pintype "bidirectional"))
      (node (ref "IC14") (pin "13") (pinfunction "RD-_13") (pintype "bidirectional"))
      (node (ref "R41") (pin "1") (pinfunction "1_1") (pintype "passive"))
      (node (ref "X5") (pin "8") (pinfunction "RD-_8") (pintype "input"))
    )
    (net (code "123") (name "Net-(IC14-CRS{slash}CRS_DV{slash}LED_CFG)") (class "Default")
      (node (ref "IC14") (pin "40") (pinfunction "CRS/CRS_DV/LED_CFG_40") (pintype "output"))
      (node (ref "RN1") (pin "5") (pinfunction "2_5") (pintype "passive"))
    )
    (net (code "124") (name "Net-(IC14-MDIX_EN(RX_ER))") (class "Default")
      (node (ref "IC14") (pin "41") (pinfunction "MDIX_EN(RX_ER)_41") (pintype "output"))
      (node (ref "RN2") (pin "8") (pinfunction "2_8") (pintype "passive"))
    )
    (net (code "125") (name "Net-(IC14-MII_MODE(RX_DV))") (class "Default")
      (node (ref "IC14") (pin "39") (pinfunction "MII_MODE(RX_DV)_39") (pintype "output"))
      (node (ref "JP11") (pin "2") (pinfunction "2_2") (pintype "passive"))
      (node (ref "RN1") (pin "6") (pinfunction "2_6") (pintype "passive"))
    )
    (net (code "126") (name "Net-(IC14-PFBIN1)") (class "Default")
      (node (ref "C62") (pin "1") (pinfunction "1_1") (pintype "passive"))
      (node (ref "C63") (pin "1") (pinfunction "1_1") (pintype "passive"))
      (node (ref "C64") (pin "+") (pinfunction "+_+") (pintype "passive"))
      (node (ref "C65") (pin "1") (pinfunction "1_1") (pintype "passive"))
      (node (ref "IC14") (pin "18") (pinfunction "PFBIN1_18") (pintype "input"))
      (node (ref "IC14") (pin "23") (pinfunction "PFBOUT_23") (pintype "output"))
      (node (ref "IC14") (pin "37") (pinfunction "PFBIN2_37") (pintype "input"))
    )
    (net (code "127") (name "Net-(IC14-PHYAD0(COL))") (class "Default")
      (node (ref "IC14") (pin "42") (pinfunction "PHYAD0(COL)_42") (pintype "output"))
      (node (ref "RN2") (pin "7") (pinfunction "2_7") (pintype "passive"))
    )
    (net (code "128") (name "Net-(IC14-PHYAD1(RXD1_0))") (class "Default")
      (node (ref "IC14") (pin "43") (pinfunction "PHYAD1(RXD1_0)_43") (pintype "output"))
      (node (ref "RN2") (pin "6") (pinfunction "2_6") (pintype "passive"))
    )
    (net (code "129") (name "Net-(IC14-PHYAD2(RXD1_1))") (class "Default")
      (node (ref "IC14") (pin "44") (pinfunction "PHYAD2(RXD1_1)_44") (pintype "output"))
      (node (ref "RN2") (pin "5") (pinfunction "2_5") (pintype "passive"))
    )
    (net (code "130") (name "Net-(IC14-PHYAD3(RXD1_2))") (class "Default")
      (node (ref "IC14") (pin "45") (pinfunction "PHYAD3(RXD1_2)_45") (pintype "output"))
      (node (ref "RN3") (pin "8") (pinfunction "2_8") (pintype "passive"))
    )
    (net (code "131") (name "Net-(IC14-PHYAD4(RXD1_3))") (class "Default")
      (node (ref "IC14") (pin "46") (pinfunction "PHYAD4(RXD1_3)_46") (pintype "output"))
      (node (ref "RN3") (pin "7") (pinfunction "2_7") (pintype "passive"))
    )
    (net (code "132") (name "Net-(IC14-PWR_DOWN{slash}INT)") (class "Default")
      (node (ref "IC14") (pin "7") (pinfunction "PWR_DOWN/INT_7") (pintype "input"))
      (node (ref "JP13") (pin "2") (pinfunction "2_2") (pintype "passive"))
    )
    (net (code "133") (name "Net-(IC14-RBIAS)") (class "Default")
      (node (ref "IC14") (pin "24") (pinfunction "RBIAS_24") (pintype "input"))
      (node (ref "R47") (pin "2") (pinfunction "2_2") (pintype "passive"))
    )
    (net (code "134") (name "Net-(IC14-RESERVED-20)") (class "Default")
      (node (ref "IC14") (pin "20") (pinfunction "RESERVED-20_20") (pintype "bidirectional"))
      (node (ref "R46") (pin "2") (pinfunction "2_2") (pintype "passive"))
    )
    (net (code "135") (name "Net-(IC14-RESERVED-21)") (class "Default")
      (node (ref "IC14") (pin "21") (pinfunction "RESERVED-21_21") (pintype "bidirectional"))
      (node (ref "R45") (pin "2") (pinfunction "2_2") (pintype "passive"))
    )
    (net (code "136") (name "Net-(IC14-RX_CLK)") (class "Default")
      (node (ref "IC14") (pin "38") (pinfunction "RX_CLK_38") (pintype "output"))
      (node (ref "RN1") (pin "7") (pinfunction "2_7") (pintype "passive"))
    )
    (net (code "137") (name "Net-(IC14-TXD_0)") (class "Default")
      (node (ref "IC14") (pin "3") (pinfunction "TXD_0_3") (pintype "input"))
      (node (ref "RN4") (pin "8") (pinfunction "2_8") (pintype "passive"))
    )
    (net (code "138") (name "Net-(IC14-TXD_1)") (class "Default")
      (node (ref "IC14") (pin "4") (pinfunction "TXD_1_4") (pintype "input"))
      (node (ref "RN4") (pin "7") (pinfunction "2_7") (pintype "passive"))
    )
    (net (code "139") (name "Net-(IC14-TXD_2)") (class "Default")
      (node (ref "IC14") (pin "5") (pinfunction "TXD_2_5") (pintype "input"))
      (node (ref "RN4") (pin "6") (pinfunction "2_6") (pintype "passive"))
    )
    (net (code "140") (name "Net-(IC14-TXD_3{slash}SNI_MODE)") (class "Default")
      (node (ref "IC14") (pin "6") (pinfunction "TXD_3/SNI_MODE_6") (pintype "input"))
      (node (ref "RN4") (pin "5") (pinfunction "2_5") (pintype "passive"))
    )
    (net (code "141") (name "Net-(IC14-TX_CLK)") (class "Default")
      (node (ref "IC14") (pin "1") (pinfunction "TX_CLK_1") (pintype "output"))
      (node (ref "RN3") (pin "6") (pinfunction "2_6") (pintype "passive"))
    )
    (net (code "142") (name "Net-(IC14-TX_EN)") (class "Default")
      (node (ref "IC14") (pin "2") (pinfunction "TX_EN_2") (pintype "input"))
      (node (ref "RN3") (pin "5") (pinfunction "2_5") (pintype "passive"))
    )
    (net (code "143") (name "Net-(IC14-X1)") (class "Default")
      (node (ref "IC14") (pin "34") (pinfunction "X1_34") (pintype "input"))
      (node (ref "RN1") (pin "8") (pinfunction "2_8") (pintype "passive"))
    )
    (net (code "144") (name "Net-(JP9-Pad2)") (class "Default")
      (node (ref "JP9") (pin "2") (pinfunction "2_2") (pintype "passive"))
      (node (ref "R37") (pin "2") (pinfunction "2_2") (pintype "passive"))
    )
    (net (code "145") (name "Net-(JP10-Pad1)") (class "Default")
      (node (ref "JP10") (pin "1") (pinfunction "1_1") (pintype "passive"))
      (node (ref "JP12") (pin "1") (pinfunction "1_1") (pintype "passive"))
      (node (ref "RN2") (pin "1") (pinfunction "1_1") (pintype "passive"))
    )
    (net (code "146") (name "Net-(JP10-Pad2)") (class "Default")
      (node (ref "JP10") (pin "2") (pinfunction "2_2") (pintype "passive"))
      (node (ref "R34") (pin "2") (pinfunction "2_2") (pintype "passive"))
    )
    (net (code "147") (name "Net-(JP11-Pad1)") (class "Default")
      (node (ref "JP11") (pin "1") (pinfunction "1_1") (pintype "passive"))
      (node (ref "R39") (pin "2") (pinfunction "2_2") (pintype "passive"))
    )
    (net (code "148") (name "Net-(JP13-Pad1)") (class "Default")
      (node (ref "JP13") (pin "1") (pinfunction "1_1") (pintype "passive"))
      (node (ref "R48") (pin "2") (pinfunction "2_2") (pintype "passive"))
    )
    (net (code "149") (name "Net-(LCD1-B0)") (class "Default")
      (node (ref "JP6") (pin "COM") (pinfunction "COM_COM") (pintype "passive"))
      (node (ref "LCD1") (pin "13") (pinfunction "G0_13") (pintype "input"))
      (node (ref "LCD1") (pin "14") (pinfunction "G1_14") (pintype "input"))
      (node (ref "LCD1") (pin "21") (pinfunction "B0_21") (pintype "input"))
      (node (ref "LCD1") (pin "22") (pinfunction "B1_22") (pintype "input"))
      (node (ref "LCD1") (pin "23") (pinfunction "B2_23") (pintype "input"))
      (node (ref "LCD1") (pin "5") (pinfunction "R0_5") (pintype "input"))
      (node (ref "LCD1") (pin "6") (pinfunction "R1_6") (pintype "input"))
      (node (ref "LCD1") (pin "7") (pinfunction "R2_7") (pintype "input"))
    )
    (net (code "150") (name "Net-(LCD1-RESET)") (class "Default")
      (node (ref "JP7") (pin "COM") (pinfunction "COM_COM") (pintype "passive"))
      (node (ref "LCD1") (pin "36") (pinfunction "RESET_36") (pintype "input"))
    )
    (net (code "151") (name "Net-(Q1-PadB)") (class "Default")
      (node (ref "Q1") (pin "B") (pinfunction "B_B") (pintype "passive"))
      (node (ref "R27") (pin "2") (pinfunction "2_2") (pintype "passive"))
    )
    (net (code "152") (name "Net-(Q1-PadC)") (class "Default")
      (node (ref "Q1") (pin "C") (pinfunction "C_C") (pintype "passive"))
      (node (ref "R24") (pin "1") (pinfunction "1_1") (pintype "passive"))
    )
    (net (code "153") (name "Net-(Q2-D)") (class "Default")
      (node (ref "Q2") (pin "3") (pinfunction "D_3") (pintype "passive"))
      (node (ref "SP1") (pin "-B") (pinfunction "-_-B") (pintype "passive"))
      (node (ref "SP1") (pin "-B.1") (pinfunction "-_-B.1") (pintype "passive"))
    )
    (net (code "154") (name "Net-(R1-Pad2)") (class "Default")
      (node (ref "R1") (pin "2") (pinfunction "2_2") (pintype "passive"))
      (node (ref "R2") (pin "2") (pinfunction "2_2") (pintype "passive"))
      (node (ref "SW2") (pin "A") (pinfunction "A_A") (pintype "passive"))
    )
    (net (code "155") (name "Net-(R3-Pad2)") (class "Default")
      (node (ref "R3") (pin "2") (pinfunction "2_2") (pintype "passive"))
      (node (ref "R4") (pin "1") (pinfunction "1_1") (pintype "passive"))
    )
    (net (code "156") (name "Net-(R7-Pad2)") (class "Default")
      (node (ref "R7") (pin "2") (pinfunction "2_2") (pintype "passive"))
      (node (ref "R8") (pin "1") (pinfunction "1_1") (pintype "passive"))
    )
    (net (code "157") (name "Net-(R10-Pad2)") (class "Default")
      (node (ref "R10") (pin "2") (pinfunction "2_2") (pintype "passive"))
      (node (ref "R6") (pin "2") (pinfunction "2_2") (pintype "passive"))
      (node (ref "SW2") (pin "B") (pinfunction "B_B") (pintype "passive"))
    )
    (net (code "158") (name "Net-(R24-Pad2)") (class "Default")
      (node (ref "R24") (pin "2") (pinfunction "2_2") (pintype "passive"))
      (node (ref "VBUS") (pin "C") (pinfunction "C_C") (pintype "passive"))
    )
    (net (code "159") (name "Net-(R38-Pad2)") (class "Default")
      (node (ref "R38") (pin "2") (pinfunction "2_2") (pintype "passive"))
      (node (ref "SPEED") (pin "A") (pinfunction "A_A") (pintype "passive"))
    )
    (net (code "160") (name "Net-(X2E-1)") (class "Default")
      (node (ref "SCL") (pin "2") (pinfunction "2_2") (pintype "passive"))
      (node (ref "X2") (pin "13") (pinfunction "1_13") (pintype "passive"))
    )
    (net (code "161") (name "Net-(X2F-1)") (class "Default")
      (node (ref "SDA") (pin "1") (pinfunction "1_1") (pintype "passive"))
      (node (ref "X2") (pin "14") (pinfunction "1_14") (pintype "passive"))
    )
    (net (code "162") (name "Net-(X4A-S)") (class "Default")
      (node (ref "JP5") (pin "2") (pinfunction "2_2") (pintype "passive"))
      (node (ref "R18") (pin "2") (pinfunction "2_2") (pintype "passive"))
      (node (ref "X4") (pin "1") (pinfunction "S_1") (pintype "passive"))
    )
    (net (code "163") (name "Net-(X5-GREEN-C)") (class "Default")
      (node (ref "R44") (pin "1") (pinfunction "1_1") (pintype "passive"))
      (node (ref "X5") (pin "10") (pinfunction "GREEN-C_10") (pintype "passive"))
    )
    (net (code "164") (name "Net-(X5-YELLOW-C)") (class "Default")
      (node (ref "R43") (pin "1") (pinfunction "1_1") (pintype "passive"))
      (node (ref "X5") (pin "11") (pinfunction "YELLOW-C_11") (pintype "passive"))
    )
    (net (code "165") (name "OE_SYNC") (class "Default")
      (node (ref "IC3") (pin "94") (pinfunction "PD13_94") (pintype "bidirectional"))
      (node (ref "X1") (pin "10") (pinfunction "1_10") (pintype "passive"))
    )
    (net (code "166") (name "PE") (class "Default")
      (node (ref "C1") (pin "1") (pinfunction "1_1") (pintype "passive"))
      (node (ref "C51") (pin "1") (pinfunction "1_1") (pintype "passive"))
      (node (ref "J2") (pin "SH1") (pinfunction "SH1_SH1") (pintype "bidirectional"))
      (node (ref "J2") (pin "SH1.1") (pinfunction "SH1_SH1.1") (pintype "bidirectional"))
      (node (ref "J2") (pin "SH2") (pinfunction "SH2_SH2") (pintype "bidirectional"))
      (node (ref "J2") (pin "SH2.2") (pinfunction "SH2_SH2.2") (pintype "bidirectional"))
      (node (ref "JP1") (pin "2") (pinfunction "2_2") (pintype "passive"))
      (node (ref "X2") (pin "1") (pinfunction "1_1") (pintype "passive"))
      (node (ref "X5") (pin "SH") (pinfunction "SH_SH") (pintype "passive"))
      (node (ref "X5") (pin "SH2") (pinfunction "SH_SH2") (pintype "passive"))
    )
    (net (code "167") (name "PWR_DIRECT") (class "Default")
      (node (ref "IC3") (pin "110") (pinfunction "PG2_110") (pintype "bidirectional"))
      (node (ref "X2") (pin "12") (pinfunction "1_12") (pintype "passive"))
    )
    (net (code "168") (name "PWR_SSTART") (class "Default")
      (node (ref "IC3") (pin "111") (pinfunction "PG3_111") (pintype "bidirectional"))
      (node (ref "X2") (pin "11") (pinfunction "1_11") (pintype "passive"))
    )
    (net (code "169") (name "RCC_OSC32_IN") (class "Default")
      (node (ref "C10") (pin "1") (pinfunction "1_1") (pintype "passive"))
      (node (ref "IC3") (pin "9") (pinfunction "PC14_9") (pintype "bidirectional"))
      (node (ref "Y2") (pin "1") (pinfunction "1_1") (pintype "passive"))
    )
    (net (code "170") (name "RCC_OSC32_OUT") (class "Default")
      (node (ref "C12") (pin "1") (pinfunction "1_1") (pintype "passive"))
      (node (ref "IC3") (pin "10") (pinfunction "PC15_10") (pintype "bidirectional"))
      (node (ref "Y2") (pin "4") (pinfunction "2_4") (pintype "passive"))
    )
    (net (code "171") (name "RCC_OSC_IN") (class "Default")
      (node (ref "C9") (pin "2") (pinfunction "2_2") (pintype "passive"))
      (node (ref "IC3") (pin "29") (pinfunction "PH0_29") (pintype "bidirectional"))
      (node (ref "Y1") (pin "2") (pinfunction "2_2") (pintype "passive"))
    )
    (net (code "172") (name "RCC_OSC_OUT") (class "Default")
      (node (ref "C11") (pin "2") (pinfunction "2_2") (pintype "passive"))
      (node (ref "IC3") (pin "30") (pinfunction "PH1_30") (pintype "bidirectional"))
      (node (ref "Y1") (pin "1") (pinfunction "1_1") (pintype "passive"))
    )
    (net (code "173") (name "SDMMC1_CK") (class "Default")
      (node (ref "IC3") (pin "141") (pinfunction "PC12_141") (pintype "bidirectional"))
      (node (ref "J1") (pin "5") (pinfunction "CLK_5") (pintype "passive"))
    )
    (net (code "174") (name "SDMMC1_CMD") (class "Default")
      (node (ref "IC3") (pin "144") (pinfunction "PD2_144") (pintype "bidirectional"))
      (node (ref "J1") (pin "3") (pinfunction "CMD_3") (pintype "passive"))
      (node (ref "R22") (pin "2") (pinfunction "2_2") (pintype "passive"))
    )
    (net (code "175") (name "SDMMC1_D0") (class "Default")
      (node (ref "IC3") (pin "121") (pinfunction "PC8_121") (pintype "bidirectional"))
      (node (ref "J1") (pin "7") (pinfunction "DAT0_7") (pintype "passive"))
      (node (ref "R21") (pin "2") (pinfunction "2_2") (pintype "passive"))
    )
    (net (code "176") (name "SD_DETECT") (class "Default")
      (node (ref "IC3") (pin "140") (pinfunction "PC11_140") (pintype "bidirectional"))
      (node (ref "J1") (pin "SW1") (pinfunction "SW1_SW1") (pintype "passive"))
    )
    (net (code "177") (name "SPI2_CLK") (class "Default")
      (node (ref "IC3") (pin "133") (pinfunction "PI1_133") (pintype "bidirectional"))
      (node (ref "X1") (pin "32") (pinfunction "1_32") (pintype "passive"))
    )
    (net (code "178") (name "SPI2_CSA") (class "Default")
      (node (ref "IC3") (pin "93") (pinfunction "PD12_93") (pintype "bidirectional"))
      (node (ref "X1") (pin "28") (pinfunction "1_28") (pintype "passive"))
    )
    (net (code "179") (name "SPI2_CSB") (class "Default")
      (node (ref "IC3") (pin "92") (pinfunction "PD11_92") (pintype "bidirectional"))
      (node (ref "X1") (pin "27") (pinfunction "1_27") (pintype "passive"))
    )
    (net (code "180") (name "SPI2_IRQ") (class "Default")
      (node (ref "IC3") (pin "123") (pinfunction "PA8_123") (pintype "bidirectional"))
      (node (ref "X1") (pin "25") (pinfunction "1_25") (pintype "passive"))
    )
    (net (code "181") (name "SPI2_MISO") (class "Default")
      (node (ref "IC3") (pin "87") (pinfunction "PB14_87") (pintype "bidirectional"))
      (node (ref "X1") (pin "31") (pinfunction "1_31") (pintype "passive"))
    )
    (net (code "182") (name "SPI2_MOSI") (class "Default")
      (node (ref "IC3") (pin "134") (pinfunction "PI3_134") (pintype "bidirectional"))
      (node (ref "X1") (pin "33") (pinfunction "1_33") (pintype "passive"))
    )
    (net (code "183") (name "SPI4_CLK") (class "Default")
      (node (ref "IC3") (pin "1") (pinfunction "PE2_1") (pintype "bidirectional"))
      (node (ref "X1") (pin "23") (pinfunction "1_23") (pintype "passive"))
    )
    (net (code "184") (name "SPI4_CSA") (class "Default")
      (node (ref "IC3") (pin "2") (pinfunction "PE3_2") (pintype "bidirectional"))
      (node (ref "X1") (pin "22") (pinfunction "1_22") (pintype "passive"))
    )
    (net (code "185") (name "SPI4_CSB") (class "Default")
      (node (ref "IC3") (pin "3") (pinfunction "PE4_3") (pintype "bidirectional"))
      (node (ref "X1") (pin "21") (pinfunction "1_21") (pintype "passive"))
    )
    (net (code "186") (name "SPI4_IRQ") (class "Default")
      (node (ref "IC3") (pin "168") (pinfunction "PB9_168") (pintype "bidirectional"))
      (node (ref "X1") (pin "19") (pinfunction "1_19") (pintype "passive"))
    )
    (net (code "187") (name "SPI4_MISO") (class "Default")
      (node (ref "IC3") (pin "4") (pinfunction "PE5_4") (pintype "bidirectional"))
      (node (ref "X1") (pin "24") (pinfunction "1_24") (pintype "passive"))
    )
    (net (code "188") (name "SPI4_MOSI") (class "Default")
      (node (ref "IC3") (pin "5") (pinfunction "PE6_5") (pintype "bidirectional"))
      (node (ref "X1") (pin "26") (pinfunction "1_26") (pintype "passive"))
    )
    (net (code "189") (name "SPI5_CLK") (class "Default")
      (node (ref "IC3") (pin "25") (pinfunction "PF7_25") (pintype "bidirectional"))
      (node (ref "X1") (pin "17") (pinfunction "1_17") (pintype "passive"))
    )
    (net (code "190") (name "SPI5_CSA") (class "Default")
      (node (ref "IC3") (pin "157") (pinfunction "PG14_157") (pintype "bidirectional"))
      (node (ref "X1") (pin "11") (pinfunction "1_11") (pintype "passive"))
    )
    (net (code "191") (name "SPI5_CSB") (class "Default")
      (node (ref "IC3") (pin "156") (pinfunction "PG13_156") (pintype "bidirectional"))
      (node (ref "X1") (pin "13") (pinfunction "1_13") (pintype "passive"))
    )
    (net (code "192") (name "SPI5_IRQ") (class "Default")
      (node (ref "IC3") (pin "138") (pinfunction "PA15_138") (pintype "bidirectional"))
      (node (ref "X1") (pin "9") (pinfunction "1_9") (pintype "passive"))
    )
    (net (code "193") (name "SPI5_MISO") (class "Default")
      (node (ref "IC3") (pin "26") (pinfunction "PF8_26") (pintype "bidirectional"))
      (node (ref "X1") (pin "18") (pinfunction "1_18") (pintype "passive"))
    )
    (net (code "194") (name "SPI5_MOSI") (class "Default")
      (node (ref "IC3") (pin "27") (pinfunction "PF9_27") (pintype "bidirectional"))
      (node (ref "X1") (pin "20") (pinfunction "1_20") (pintype "passive"))
    )
    (net (code "195") (name "SYS_JTCK-SWCLK") (class "Default")
      (node (ref "IC3") (pin "137") (pinfunction "PA14_137") (pintype "bidirectional"))
      (node (ref "R20") (pin "1") (pinfunction "1_1") (pintype "passive"))
    )
    (net (code "196") (name "SYS_JTDO-SWO") (class "Default")
      (node (ref "IC3") (pin "161") (pinfunction "PB3_161") (pintype "bidirectional"))
      (node (ref "IC5") (pin "5") (pinfunction "IO4_5") (pintype "bidirectional"))
      (node (ref "X4") (pin "6") (pinfunction "S_6") (pintype "passive"))
    )
    (net (code "197") (name "SYS_JTMS-SWDIO") (class "Default")
      (node (ref "IC3") (pin "128") (pinfunction "PA13_128") (pintype "bidirectional"))
      (node (ref "R19") (pin "1") (pinfunction "1_1") (pintype "passive"))
    )
    (net (code "198") (name "TCK") (class "Default")
      (node (ref "IC5") (pin "1") (pinfunction "IO1_1") (pintype "bidirectional"))
      (node (ref "R20") (pin "2") (pinfunction "2_2") (pintype "passive"))
      (node (ref "X4") (pin "2") (pinfunction "S_2") (pintype "passive"))
    )
    (net (code "199") (name "TFT_BRIGHTNESS") (class "Default")
      (node (ref "IC3") (pin "88") (pinfunction "PB15_88") (pintype "bidirectional"))
      (node (ref "IC9") (pin "4") (pinfunction "CTRL_4") (pintype "input"))
    )
    (net (code "200") (name "TMS") (class "Default")
      (node (ref "IC5") (pin "2") (pinfunction "IO2_2") (pintype "bidirectional"))
      (node (ref "R19") (pin "2") (pinfunction "2_2") (pintype "passive"))
      (node (ref "X4") (pin "4") (pinfunction "S_4") (pintype "passive"))
    )
    (net (code "201") (name "UART_RX{slash}DIN1") (class "Default")
      (node (ref "IC3") (pin "24") (pinfunction "PF6_24") (pintype "bidirectional"))
      (node (ref "R5") (pin "2") (pinfunction "2_2") (pintype "passive"))
      (node (ref "X1") (pin "3") (pinfunction "1_3") (pintype "passive"))
    )
    (net (code "202") (name "UART_TX{slash}DOUT1") (class "Default")
      (node (ref "IC2") (pin "11") (pinfunction "I_11") (pintype "input"))
      (node (ref "IC2") (pin "5") (pinfunction "I_5") (pintype "input"))
      (node (ref "IC3") (pin "162") (pinfunction "PB4_162") (pintype "bidirectional"))
      (node (ref "X1") (pin "4") (pinfunction "1_4") (pintype "passive"))
    )
    (net (code "203") (name "USB_D_N") (class "Default")
      (node (ref "IC10") (pin "1") (pinfunction "IO1_1") (pintype "bidirectional"))
      (node (ref "J2") (pin "2") (pinfunction "D-_2") (pintype "passive"))
      (node (ref "R28") (pin "1") (pinfunction "1_1") (pintype "passive"))
    )
    (net (code "204") (name "USB_D_P") (class "Default")
      (node (ref "IC10") (pin "2") (pinfunction "IO2_2") (pintype "bidirectional"))
      (node (ref "J2") (pin "3") (pinfunction "D+_3") (pintype "passive"))
      (node (ref "R29") (pin "1") (pinfunction "1_1") (pintype "passive"))
    )
    (net (code "205") (name "USB_OTG_FS_D_N") (class "Default")
      (node (ref "IC3") (pin "126") (pinfunction "PA11_126") (pintype "bidirectional"))
      (node (ref "R28") (pin "2") (pinfunction "2_2") (pintype "passive"))
    )
    (net (code "206") (name "USB_OTG_FS_D_P") (class "Default")
      (node (ref "IC3") (pin "127") (pinfunction "PA12_127") (pintype "bidirectional"))
      (node (ref "R29") (pin "2") (pinfunction "2_2") (pintype "passive"))
    )
    (net (code "207") (name "USB_OTG_FS_ID") (class "Default")
      (node (ref "IC10") (pin "4") (pinfunction "IO3_4") (pintype "bidirectional"))
      (node (ref "IC3") (pin "125") (pinfunction "PA10_125") (pintype "bidirectional"))
      (node (ref "J2") (pin "4") (pinfunction "ID_4") (pintype "passive"))
    )
    (net (code "208") (name "USB_OTG_FS_PSO") (class "Default")
      (node (ref "IC3") (pin "147") (pinfunction "PD5_147") (pintype "bidirectional"))
      (node (ref "IC8") (pin "4") (pinfunction "EN_4") (pintype "input"))
    )
    (net (code "209") (name "USB_OTG_FS_VBUS") (class "Default")
      (node (ref "C49") (pin "+") (pinfunction "+_+") (pintype "passive"))
      (node (ref "C52") (pin "2") (pinfunction "2_2") (pintype "passive"))
      (node (ref "IC10") (pin "6") (pinfunction "VCC_6") (pintype "passive"))
      (node (ref "IC3") (pin "124") (pinfunction "PA9_124") (pintype "bidirectional"))
      (node (ref "IC8") (pin "1") (pinfunction "OUT_1") (pintype "output"))
      (node (ref "J2") (pin "1") (pinfunction "VCC_1") (pintype "passive"))
      (node (ref "R27") (pin "1") (pinfunction "1_1") (pintype "passive"))
    )
    (net (code "210") (name "USER_SW") (class "Default")
      (node (ref "C4") (pin "2") (pinfunction "2_2") (pintype "passive"))
      (node (ref "IC3") (pin "152") (pinfunction "PG9_152") (pintype "bidirectional"))
      (node (ref "SW1") (pin "1") (pinfunction "1_1") (pintype "passive"))
    )
    (net (code "211") (name "VBAT") (class "Default")
      (node (ref "IC3") (pin "6") (pinfunction "VBAT_6") (pintype "power_in"))
      (node (ref "JP4") (pin "COM") (pinfunction "COM_COM") (pintype "passive"))
    )
    (net (code "212") (name "VCAP1") (class "Default")
      (node (ref "C37") (pin "1") (pinfunction "1_1") (pintype "passive"))
      (node (ref "IC3") (pin "81") (pinfunction "VCAP_1_81") (pintype "power_in"))
    )
    (net (code "213") (name "VCAP2") (class "Default")
      (node (ref "C36") (pin "1") (pinfunction "1_1") (pintype "passive"))
      (node (ref "IC3") (pin "129") (pinfunction "VCAP_2_129") (pintype "power_in"))
    )
    (net (code "214") (name "VDD") (class "Default")
      (node (ref "C16") (pin "1") (pinfunction "1_1") (pintype "passive"))
      (node (ref "C17") (pin "1") (pinfunction "1_1") (pintype "passive"))
      (node (ref "C18") (pin "1") (pinfunction "1_1") (pintype "passive"))
      (node (ref "C19") (pin "1") (pinfunction "1_1") (pintype "passive"))
      (node (ref "C20") (pin "1") (pinfunction "1_1") (pintype "passive"))
      (node (ref "C21") (pin "1") (pinfunction "1_1") (pintype "passive"))
      (node (ref "C22") (pin "+") (pinfunction "+_+") (pintype "passive"))
      (node (ref "C23") (pin "1") (pinfunction "1_1") (pintype "passive"))
      (node (ref "C24") (pin "1") (pinfunction "1_1") (pintype "passive"))
      (node (ref "C25") (pin "1") (pinfunction "1_1") (pintype "passive"))
      (node (ref "C26") (pin "1") (pinfunction "1_1") (pintype "passive"))
      (node (ref "C27") (pin "1") (pinfunction "1_1") (pintype "passive"))
      (node (ref "C28") (pin "1") (pinfunction "1_1") (pintype "passive"))
      (node (ref "C29") (pin "1") (pinfunction "1_1") (pintype "passive"))
      (node (ref "C30") (pin "1") (pinfunction "1_1") (pintype "passive"))
      (node (ref "C31") (pin "1") (pinfunction "1_1") (pintype "passive"))
      (node (ref "C32") (pin "1") (pinfunction "1_1") (pintype "passive"))
      (node (ref "C33") (pin "1") (pinfunction "1_1") (pintype "passive"))
      (node (ref "C8") (pin "2") (pinfunction "2_2") (pintype "passive"))
      (node (ref "FB1") (pin "P$1") (pinfunction "1_P$1") (pintype "passive"))
      (node (ref "IC3") (pin "118") (pinfunction "VDDUSB_118") (pintype "power_in"))
      (node (ref "IC3") (pin "131") (pinfunction "VDD_10_131") (pintype "power_in"))
      (node (ref "IC3") (pin "136") (pinfunction "VDD_11_136") (pintype "power_in"))
      (node (ref "IC3") (pin "149") (pinfunction "VDDSDMMC_149") (pintype "power_in"))
      (node (ref "IC3") (pin "15") (pinfunction "VDD_2_15") (pintype "power_in"))
      (node (ref "IC3") (pin "159") (pinfunction "VDD_12_159") (pintype "power_in"))
      (node (ref "IC3") (pin "171") (pinfunction "PDR_ON_171") (pintype "passive"))
      (node (ref "IC3") (pin "172") (pinfunction "VDD_172") (pintype "power_in"))
      (node (ref "IC3") (pin "23") (pinfunction "VDD_3_23") (pintype "power_in"))
      (node (ref "IC3") (pin "36") (pinfunction "VDD_4_36") (pintype "power_in"))
      (node (ref "IC3") (pin "49") (pinfunction "VDD_5_49") (pintype "power_in"))
      (node (ref "IC3") (pin "62") (pinfunction "VDD_6_62") (pintype "power_in"))
      (node (ref "IC3") (pin "72") (pinfunction "VDD_7_72") (pintype "power_in"))
      (node (ref "IC3") (pin "82") (pinfunction "VDD_8_82") (pintype "power_in"))
      (node (ref "IC3") (pin "96") (pinfunction "VDD_9_96") (pintype "power_in"))
      (node (ref "IC3") (pin "99") (pinfunction "VDDDSI_99") (pintype "power_in"))
      (node (ref "JP2") (pin "1") (pinfunction "1_1") (pintype "passive"))
      (node (ref "JP4") (pin "NO") (pinfunction "NO_NO") (pintype "passive"))
      (node (ref "R11") (pin "1") (pinfunction "1_1") (pintype "passive"))
    )
    (net (code "215") (name "VDDA") (class "Default")
      (node (ref "C34") (pin "1") (pinfunction "1_1") (pintype "passive"))
      (node (ref "C35") (pin "1") (pinfunction "1_1") (pintype "passive"))
      (node (ref "FB1") (pin "P$2") (pinfunction "2_P$2") (pintype "passive"))
      (node (ref "IC3") (pin "39") (pinfunction "VDDA_39") (pintype "power_in"))
      (node (ref "R17") (pin "2") (pinfunction "2_2") (pintype "passive"))
    )
    (net (code "216") (name "VLED+") (class "Default")
      (node (ref "C48") (pin "1") (pinfunction "1_1") (pintype "passive"))
      (node (ref "D2") (pin "C") (pinfunction "C_C") (pintype "passive"))
      (node (ref "LCD1") (pin "2") (pinfunction "VLED+_2") (pintype "power_in"))
      (node (ref "ZD1") (pin "C") (pinfunction "C_C") (pintype "passive"))
    )
    (net (code "217") (name "VLED-") (class "Default")
      (node (ref "IC9") (pin "3") (pinfunction "FB_3") (pintype "input"))
      (node (ref "LCD1") (pin "1") (pinfunction "VLED-_1") (pintype "power_in"))
      (node (ref "R25") (pin "1") (pinfunction "1_1") (pintype "passive"))
      (node (ref "ZD1") (pin "A") (pinfunction "A_A") (pintype "passive"))
    )
    (net (code "218") (name "VREF+") (class "Default")
      (node (ref "IC3") (pin "38") (pinfunction "VREF+_38") (pintype "power_in"))
      (node (ref "R17") (pin "1") (pinfunction "1_1") (pintype "passive"))
    )
    (net (code "219") (name "XL") (class "Default")
      (node (ref "IC11") (pin "4") (pinfunction "IO3_4") (pintype "bidirectional"))
      (node (ref "IC12") (pin "4") (pinfunction "X-_4") (pintype "input"))
      (node (ref "LCD1") (pin "39") (pinfunction "XL_39") (pintype "passive"))
    )
    (net (code "220") (name "XR") (class "Default")
      (node (ref "IC11") (pin "1") (pinfunction "IO1_1") (pintype "bidirectional"))
      (node (ref "IC12") (pin "2") (pinfunction "X+_2") (pintype "input"))
      (node (ref "LCD1") (pin "37") (pinfunction "XR_37") (pintype "passive"))
    )
    (net (code "221") (name "YD") (class "Default")
      (node (ref "IC11") (pin "2") (pinfunction "IO2_2") (pintype "bidirectional"))
      (node (ref "IC12") (pin "5") (pinfunction "Y-_5") (pintype "input"))
      (node (ref "LCD1") (pin "38") (pinfunction "YD_38") (pintype "passive"))
    )
    (net (code "222") (name "YU") (class "Default")
      (node (ref "IC11") (pin "5") (pinfunction "IO4_5") (pintype "bidirectional"))
      (node (ref "IC12") (pin "3") (pinfunction "Y+_3") (pintype "input"))
      (node (ref "LCD1") (pin "40") (pinfunction "YU_40") (pintype "passive"))
    )
    (net (code "223") (name "unconnected-(IC3A-PC10-Pad139)") (class "Default")
      (node (ref "IC3") (pin "139") (pinfunction "PC10_139") (pintype "bidirectional"))
    )
    (net (code "224") (name "unconnected-(IC3A-PD6-Pad150)") (class "Default")
      (node (ref "IC3") (pin "150") (pinfunction "PD6_150") (pintype "bidirectional"))
    )
    (net (code "225") (name "unconnected-(IC3C-DSI_CKN-Pad105)") (class "Default")
      (node (ref "IC3") (pin "105") (pinfunction "DSI_CKN_105") (pintype "bidirectional"))
    )
    (net (code "226") (name "unconnected-(IC3C-DSI_CKP-Pad104)") (class "Default")
      (node (ref "IC3") (pin "104") (pinfunction "DSI_CKP_104") (pintype "bidirectional"))
    )
    (net (code "227") (name "unconnected-(IC3C-DSI_D0N-Pad102)") (class "Default")
      (node (ref "IC3") (pin "102") (pinfunction "DSI_D0N_102") (pintype "bidirectional"))
    )
    (net (code "228") (name "unconnected-(IC3C-DSI_D0P-Pad101)") (class "Default")
      (node (ref "IC3") (pin "101") (pinfunction "DSI_D0P_101") (pintype "bidirectional"))
    )
    (net (code "229") (name "unconnected-(IC3C-DSI_D1N-Pad108)") (class "Default")
      (node (ref "IC3") (pin "108") (pinfunction "DSI_D1N_108") (pintype "bidirectional"))
    )
    (net (code "230") (name "unconnected-(IC3C-DSI_D1P-Pad107)") (class "Default")
      (node (ref "IC3") (pin "107") (pinfunction "DSI_D1P_107") (pintype "bidirectional"))
    )
    (net (code "231") (name "unconnected-(IC3C-PI8-Pad7)") (class "Default")
      (node (ref "IC3") (pin "7") (pinfunction "PI8_7") (pintype "bidirectional"))
    )
    (net (code "232") (name "unconnected-(IC6-A12{slash}NC-36-Pad36)") (class "Default")
      (node (ref "IC6") (pin "36") (pinfunction "A12/NC-36_36") (pintype "passive"))
    )
    (net (code "233") (name "unconnected-(IC6-NC-40-Pad40)") (class "Default")
      (node (ref "IC6") (pin "40") (pinfunction "NC-40_40") (pintype "no_connect"))
    )
    (net (code "234") (name "unconnected-(IC10-IO4-Pad5)") (class "Default")
      (node (ref "IC10") (pin "5") (pinfunction "IO4_5") (pintype "bidirectional"))
    )
    (net (code "235") (name "unconnected-(IC12-AUX-Pad16)") (class "Default")
      (node (ref "IC12") (pin "16") (pinfunction "AUX_16") (pintype "input"))
    )
    (net (code "236") (name "unconnected-(IC14-CLK_OUT-Pad25)") (class "Default")
      (node (ref "IC14") (pin "25") (pinfunction "CLK_OUT_25") (pintype "output"))
    )
    (net (code "237") (name "unconnected-(IC14-TCK-Pad8)") (class "Default")
      (node (ref "IC14") (pin "8") (pinfunction "TCK_8") (pintype "input"))
    )
    (net (code "238") (name "unconnected-(IC14-TDI-Pad12)") (class "Default")
      (node (ref "IC14") (pin "12") (pinfunction "TDI_12") (pintype "input"))
    )
    (net (code "239") (name "unconnected-(IC14-TDO-Pad9)") (class "Default")
      (node (ref "IC14") (pin "9") (pinfunction "TDO_9") (pintype "output"))
    )
    (net (code "240") (name "unconnected-(IC14-TMS-Pad10)") (class "Default")
      (node (ref "IC14") (pin "10") (pinfunction "TMS_10") (pintype "input"))
    )
    (net (code "241") (name "unconnected-(IC14-X2-Pad33)") (class "Default")
      (node (ref "IC14") (pin "33") (pinfunction "X2_33") (pintype "output"))
    )
    (net (code "242") (name "unconnected-(IC14-~{TRST}-Pad11)") (class "Default")
      (node (ref "IC14") (pin "11") (pinfunction "~{TRST}_11") (pintype "input"))
    )
    (net (code "243") (name "unconnected-(J1-CD{slash}DAT3-Pad2)") (class "Default")
      (node (ref "J1") (pin "2") (pinfunction "CD/DAT3_2") (pintype "passive"))
    )
    (net (code "244") (name "unconnected-(J1-DAT1-Pad8)") (class "Default")
      (node (ref "J1") (pin "8") (pinfunction "DAT1_8") (pintype "passive"))
    )
    (net (code "245") (name "unconnected-(J1-DAT2-Pad1)") (class "Default")
      (node (ref "J1") (pin "1") (pinfunction "DAT2_1") (pintype "passive"))
    )
    (net (code "246") (name "unconnected-(LCD1-NC1-Pad35)") (class "Default")
      (node (ref "LCD1") (pin "35") (pinfunction "NC1_35") (pintype "no_connect"))
    )
    (net (code "247") (name "unconnected-(X2I-1-Pad2)") (class "Default")
      (node (ref "X2") (pin "2") (pinfunction "1_2") (pintype "passive"))
    )
    (net (code "248") (name "~{FAULT}") (class "Default")
      (node (ref "IC3") (pin "58") (pinfunction "PB2_58") (pintype "bidirectional"))
      (node (ref "R14") (pin "2") (pinfunction "2_2") (pintype "passive"))
      (node (ref "X1") (pin "8") (pinfunction "1_8") (pintype "passive"))
      (node (ref "X2") (pin "15") (pinfunction "1_15") (pintype "passive"))
    )
    (net (code "249") (name "~{RESET}") (class "Default")
      (node (ref "C8") (pin "1") (pinfunction "1_1") (pintype "passive"))
      (node (ref "IC14") (pin "29") (pinfunction "RESET_N_29") (pintype "input"))
      (node (ref "IC3") (pin "31") (pinfunction "NRST_31") (pintype "bidirectional"))
      (node (ref "IC5") (pin "4") (pinfunction "IO3_4") (pintype "bidirectional"))
      (node (ref "JP7") (pin "NO") (pinfunction "NO_NO") (pintype "passive"))
      (node (ref "R11") (pin "2") (pinfunction "2_2") (pintype "passive"))
      (node (ref "X1") (pin "6") (pinfunction "1_6") (pintype "passive"))
      (node (ref "X4") (pin "5") (pinfunction "S_5") (pintype "passive"))
    )
    (net (code "250") (name "~{USB_OTG_FS_OC}") (class "Default")
      (node (ref "IC3") (pin "146") (pinfunction "PD4_146") (pintype "bidirectional"))
      (node (ref "IC8") (pin "3") (pinfunction "~{OC}_3") (pintype "passive"))
      (node (ref "R26") (pin "1") (pinfunction "1_1") (pintype "passive"))
    )
  )
)
